# Daughter_Card_v5.net
KiCad netlist of a schematic drawn in EAGLE
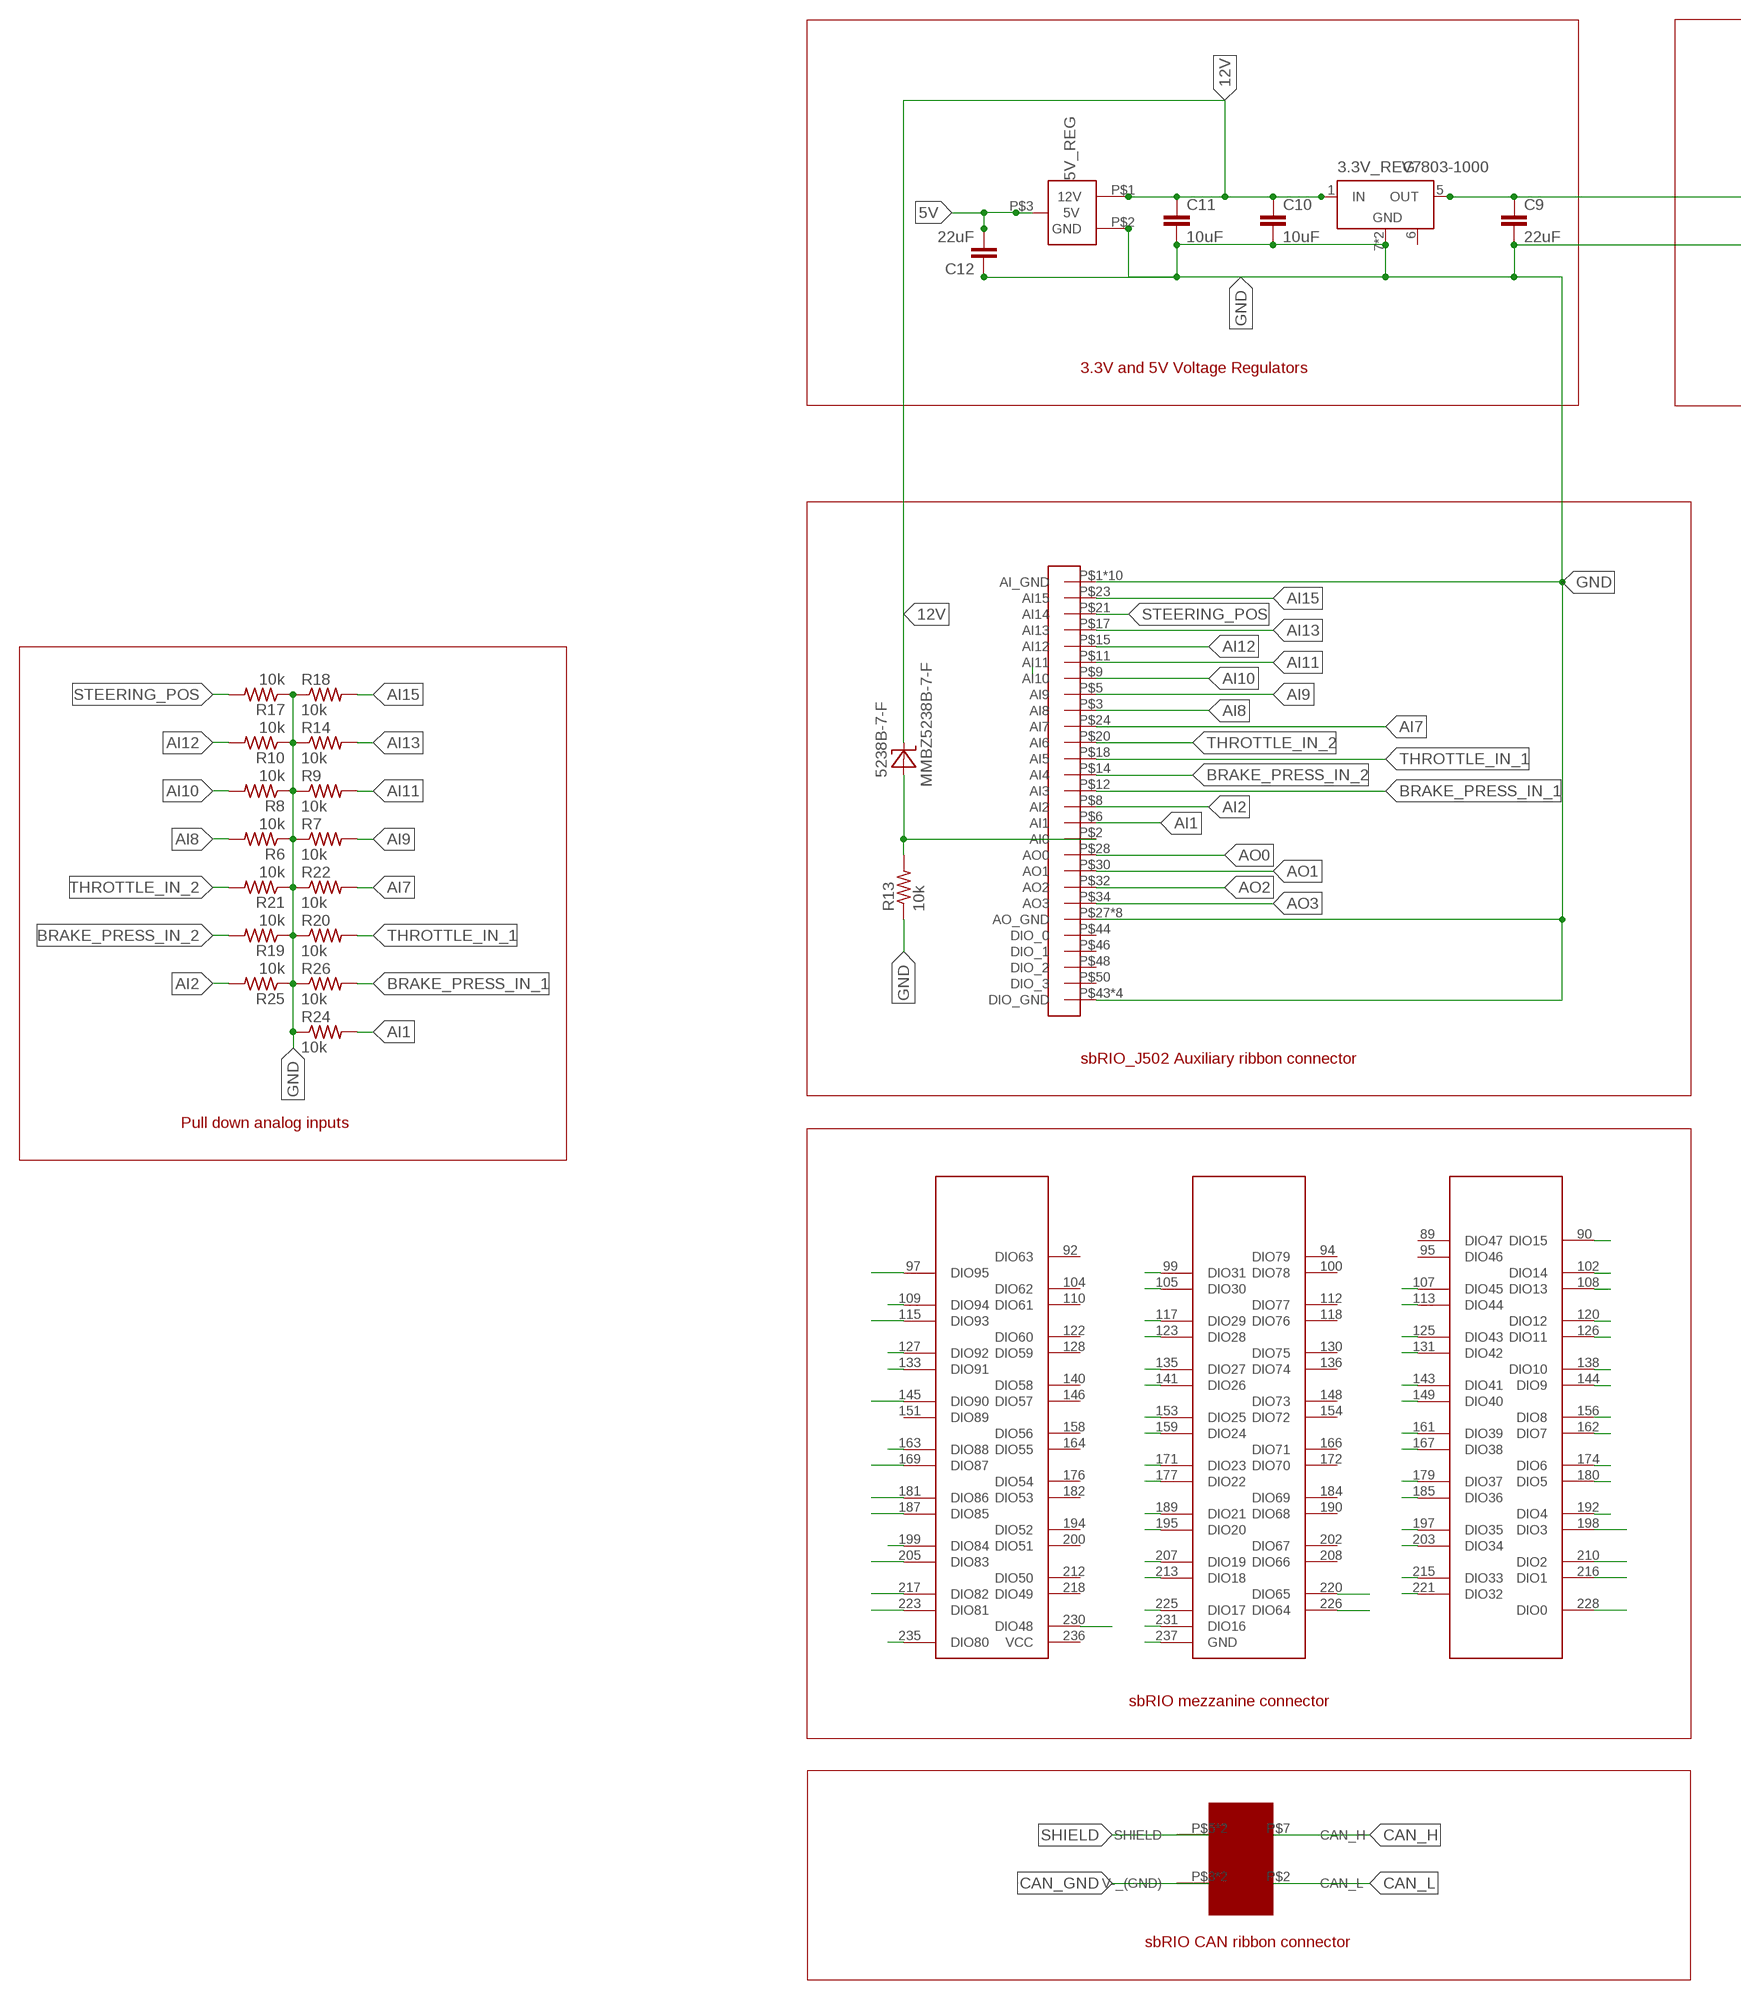
[diagram p0: schematic, sheet 1, part 1 of 2]
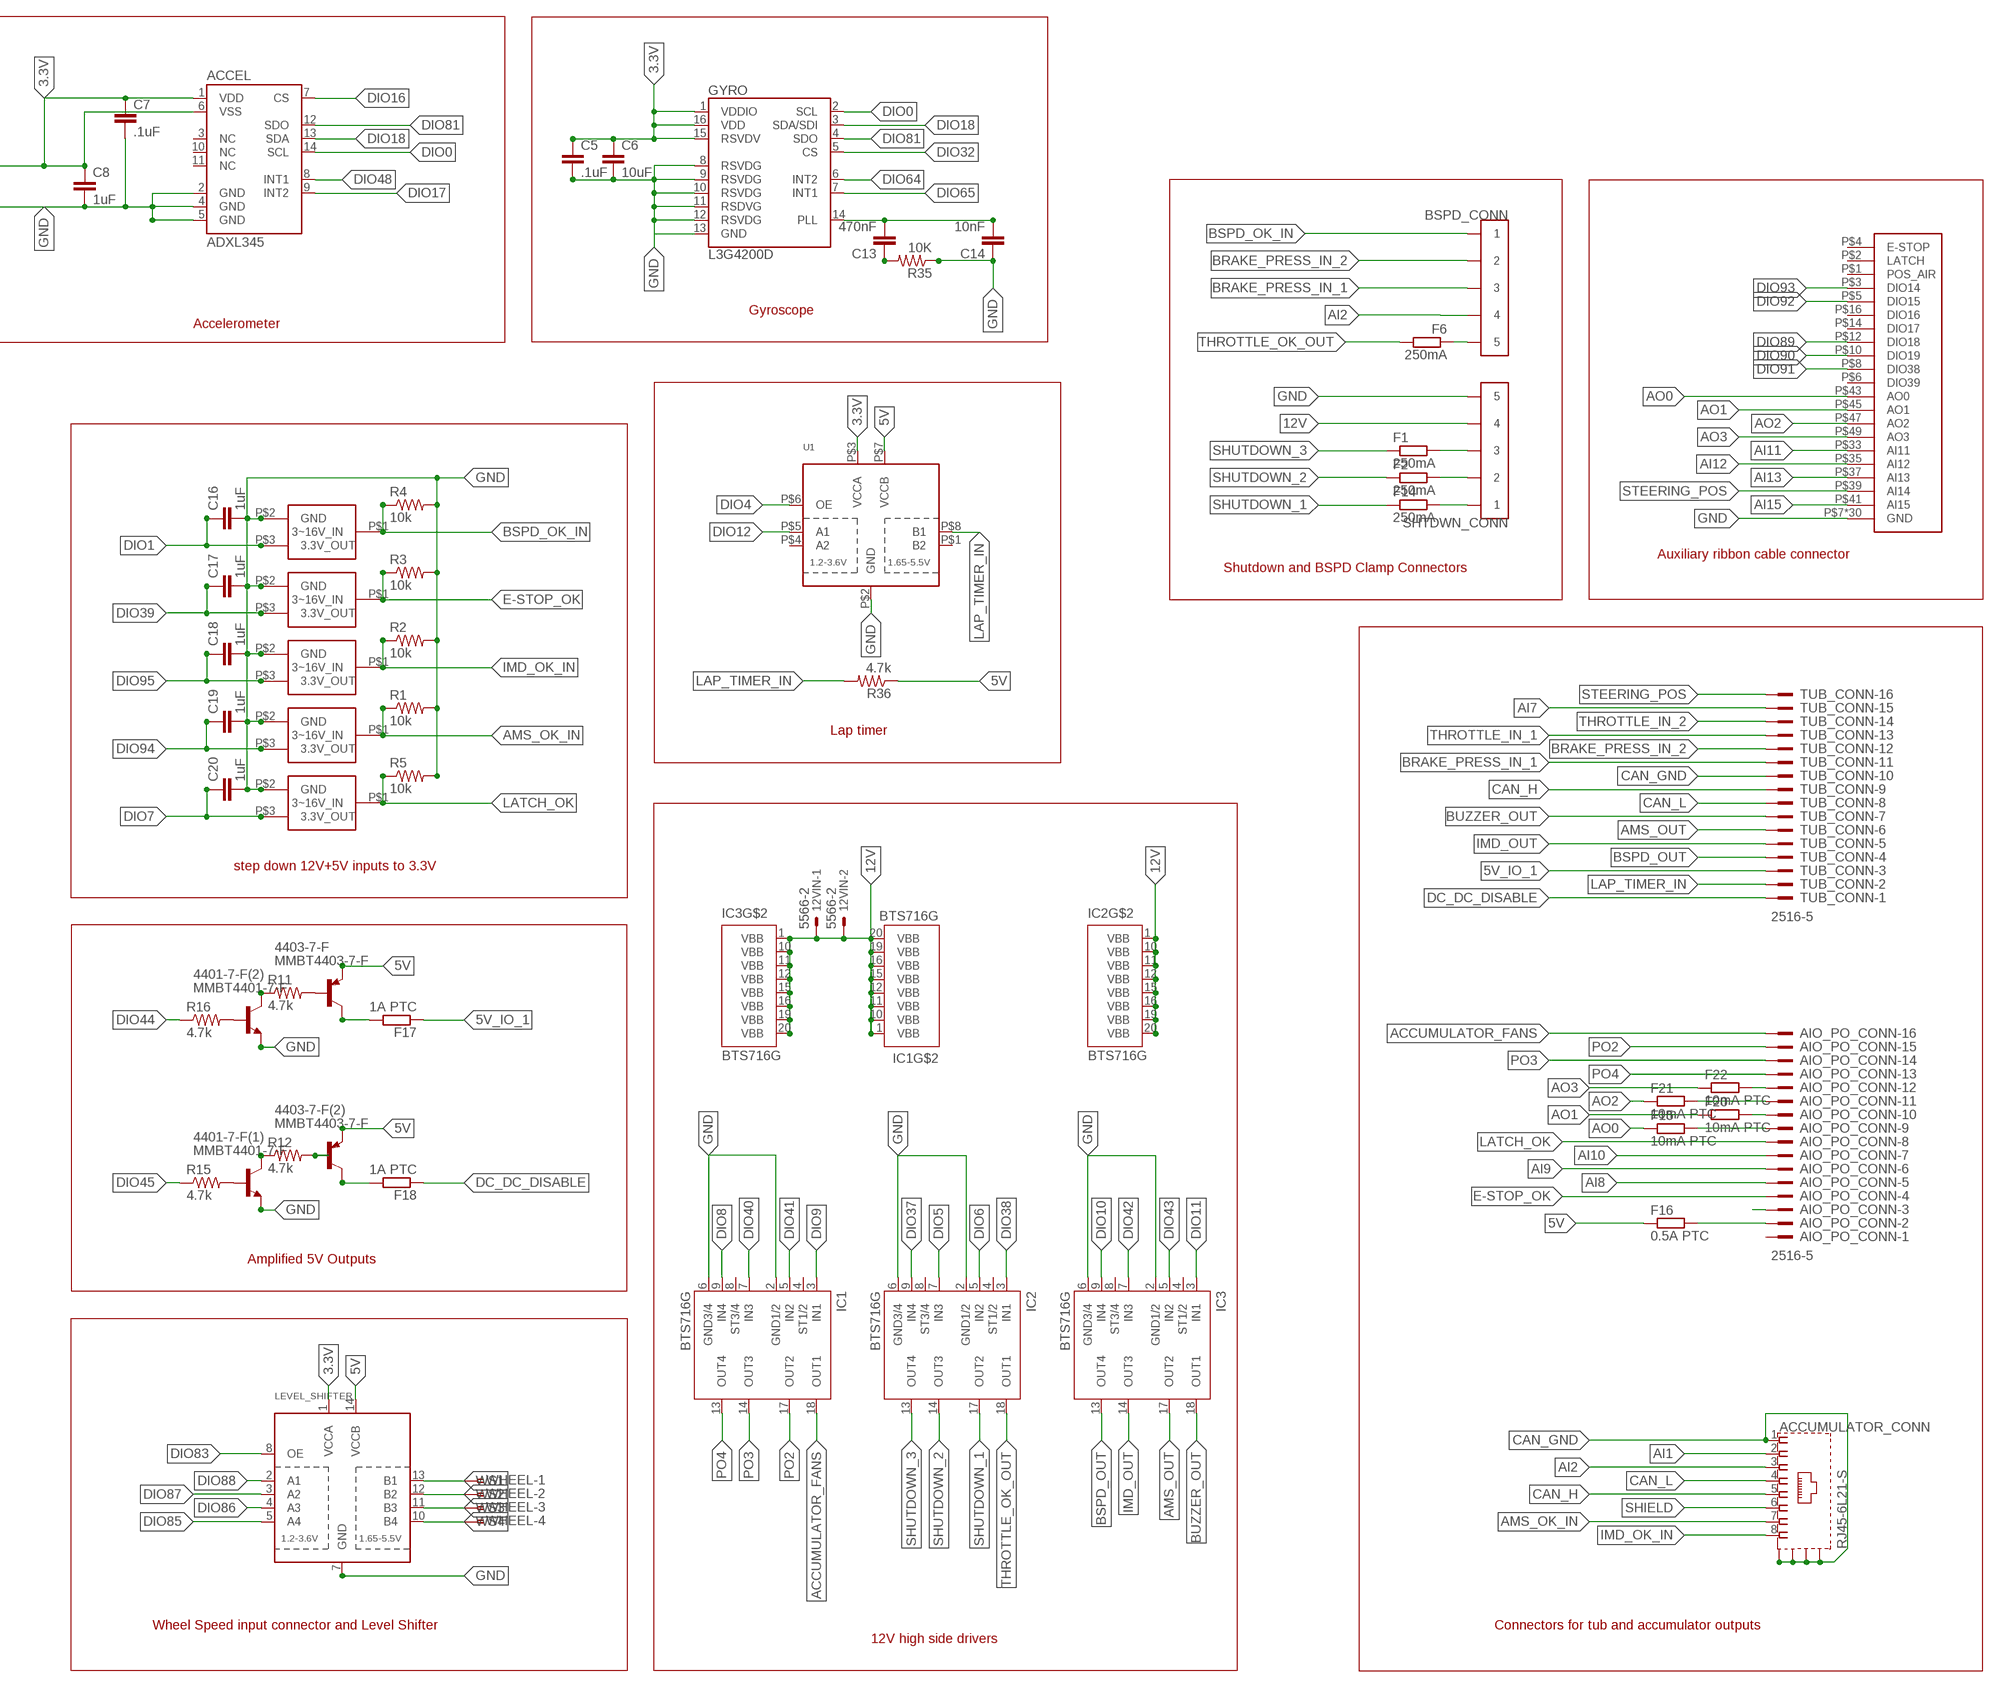
[diagram p1: schematic, sheet 1, part 2 of 2]

(export (version "E")
  (design (tool "Eeschema 10.0.6"))
  (components
    (comp (ref "3.3V_REG")
      (value "V7803-1000")
      (footprint "eagle-import:V78XX-1000")
      (libsource (lib "eagle-import") (part "V7803-1000"))
    )
    (comp (ref "5V_REG")
      (value "V78XX-1500")
      (footprint "eagle-import:V78XX-1500R")
      (libsource (lib "eagle-import") (part "V78XX-1500"))
    )
    (comp (ref "12VIN")
      (value "5566-2")
      (footprint "eagle-import:5566-2")
      (libsource (lib "eagle-import") (part "5566-2"))
    )
    (comp (ref "4401-7-F(1)")
      (value "MMBT4401-7-F")
      (footprint "eagle-import:SOT-23-3")
      (libsource (lib "eagle-import") (part "MMBT4401-7-F"))
    )
    (comp (ref "4401-7-F(2)")
      (value "MMBT4401-7-F")
      (footprint "eagle-import:SOT-23-3")
      (libsource (lib "eagle-import") (part "MMBT4401-7-F"))
    )
    (comp (ref "4403-7-F")
      (value "MMBT4403-7-F")
      (footprint "eagle-import:SOT-23-3")
      (libsource (lib "eagle-import") (part "MMBT4403-7-F"))
    )
    (comp (ref "4403-7-F(2)")
      (value "MMBT4403-7-F")
      (footprint "eagle-import:SOT-23-3")
      (libsource (lib "eagle-import") (part "MMBT4403-7-F"))
    )
    (comp (ref "5225-3.3M5-TR(5)")
      (value "MIC5225-3.3YM5-TR")
      (footprint "eagle-import:SOT-23-3")
      (libsource (lib "eagle-import") (part "MIC5225-3.3YM5-TR"))
    )
    (comp (ref "5238B-7-F")
      (value "MMBZ5238B-7-F")
      (footprint "eagle-import:SOT-23-3")
      (libsource (lib "eagle-import") (part "MMBZ5238B-7-F"))
    )
    (comp (ref "5525-3.3YM5-TR(1)")
      (value "MIC5225-3.3YM5-TR")
      (footprint "eagle-import:SOT-23-3")
      (libsource (lib "eagle-import") (part "MIC5225-3.3YM5-TR"))
    )
    (comp (ref "5525-3.3YM5-TR(2)")
      (value "MIC5225-3.3YM5-TR")
      (footprint "eagle-import:SOT-23-3")
      (libsource (lib "eagle-import") (part "MIC5225-3.3YM5-TR"))
    )
    (comp (ref "5525-3.3YM5-TR(3)")
      (value "MIC5225-3.3YM5-TR")
      (footprint "eagle-import:SOT-23-3")
      (libsource (lib "eagle-import") (part "MIC5225-3.3YM5-TR"))
    )
    (comp (ref "5525-3.3YM5-TR(4)")
      (value "MIC5225-3.3YM5-TR")
      (footprint "eagle-import:SOT-23-3")
      (libsource (lib "eagle-import") (part "MIC5225-3.3YM5-TR"))
    )
    (comp (ref "ACCEL")
      (value "ADXL345")
      (footprint "eagle-import:LGA14")
      (libsource (lib "eagle-import") (part "ADXL345"))
    )
    (comp (ref "ACCUMULATOR_CONN")
      (value "RJ45-6L21-S")
      (footprint "eagle-import:RJ45-SHIELD1")
      (libsource (lib "eagle-import") (part "RJ4521-S-6L"))
    )
    (comp (ref "AIO_PO_CONN")
      (value "2516-5")
      (footprint "eagle-import:PAK100_2500-5-16")
      (fields (field (name "MPN") "D2516-5002-AR"))
      (libsource (lib "eagle-import") (part "2516-5"))
    )
    (comp (ref "BSPD_CONN")
      (value "CONN_5")
      (footprint "eagle-import:CONNECTOR_5")
      (libsource (lib "eagle-import") (part "CONN_5"))
    )
    (comp (ref "C5")
      (value ".1uF")
      (footprint "eagle-import:0603-CAP")
      (libsource (lib "eagle-import") (part "CAP0603-CAP"))
    )
    (comp (ref "C6")
      (value "10uF")
      (footprint "eagle-import:0603-CAP")
      (libsource (lib "eagle-import") (part "CAP0603-CAP"))
    )
    (comp (ref "C7")
      (value ".1uF")
      (footprint "eagle-import:0603-CAP")
      (libsource (lib "eagle-import") (part "CAP0603-CAP"))
    )
    (comp (ref "C8")
      (value "1uF")
      (footprint "eagle-import:0603-CAP")
      (libsource (lib "eagle-import") (part "CAP0603-CAP"))
    )
    (comp (ref "C9")
      (value "22uF")
      (footprint "eagle-import:0603-CAP")
      (libsource (lib "eagle-import") (part "CAP0603-CAP"))
    )
    (comp (ref "C10")
      (value "10uF")
      (footprint "eagle-import:0603-CAP")
      (libsource (lib "eagle-import") (part "CAP0603-CAP"))
    )
    (comp (ref "C11")
      (value "10uF")
      (footprint "eagle-import:0603-CAP")
      (libsource (lib "eagle-import") (part "CAP0603-CAP"))
    )
    (comp (ref "C12")
      (value "22uF")
      (footprint "eagle-import:0603-CAP")
      (libsource (lib "eagle-import") (part "CAP0603-CAP"))
    )
    (comp (ref "C13")
      (value "470nF")
      (footprint "eagle-import:0603-CAP")
      (libsource (lib "eagle-import") (part "CAP0603-CAP"))
    )
    (comp (ref "C14")
      (value "10nF")
      (footprint "eagle-import:0603-CAP")
      (libsource (lib "eagle-import") (part "CAP0603-CAP"))
    )
    (comp (ref "C16")
      (value "1uF")
      (footprint "eagle-import:0603-CAP")
      (libsource (lib "eagle-import") (part "CAP0603-CAP"))
    )
    (comp (ref "C17")
      (value "1uF")
      (footprint "eagle-import:0603-CAP")
      (libsource (lib "eagle-import") (part "CAP0603-CAP"))
    )
    (comp (ref "C18")
      (value "1uF")
      (footprint "eagle-import:0603-CAP")
      (libsource (lib "eagle-import") (part "CAP0603-CAP"))
    )
    (comp (ref "C19")
      (value "1uF")
      (footprint "eagle-import:0603-CAP")
      (libsource (lib "eagle-import") (part "CAP0603-CAP"))
    )
    (comp (ref "C20")
      (value "1uF")
      (footprint "eagle-import:0603-CAP")
      (libsource (lib "eagle-import") (part "CAP0603-CAP"))
    )
    (comp (ref "F1")
      (value "250mA")
      (footprint "eagle-import:R0603")
      (libsource (lib "eagle-import") (part "R-EU_R0603"))
    )
    (comp (ref "F2")
      (value "250mA")
      (footprint "eagle-import:R0603")
      (libsource (lib "eagle-import") (part "R-EU_R0603"))
    )
    (comp (ref "F6")
      (value "250mA")
      (footprint "eagle-import:R0603")
      (libsource (lib "eagle-import") (part "R-EU_R0603"))
    )
    (comp (ref "F14")
      (value "250mA")
      (footprint "eagle-import:R0603")
      (libsource (lib "eagle-import") (part "R-EU_R0603"))
    )
    (comp (ref "F15")
      (value "10mA PTC")
      (footprint "eagle-import:R0402")
      (libsource (lib "eagle-import") (part "R-EU_R0402"))
    )
    (comp (ref "F16")
      (value "0.5A PTC")
      (footprint "eagle-import:R0603")
      (libsource (lib "eagle-import") (part "R-EU_R0603"))
    )
    (comp (ref "F17")
      (value "1A PTC")
      (footprint "eagle-import:R0603")
      (libsource (lib "eagle-import") (part "R-EU_R0603"))
    )
    (comp (ref "F18")
      (value "1A PTC")
      (footprint "eagle-import:R0603")
      (libsource (lib "eagle-import") (part "R-EU_R0603"))
    )
    (comp (ref "F20")
      (value "10mA PTC")
      (footprint "eagle-import:R0402")
      (libsource (lib "eagle-import") (part "R-EU_R0402"))
    )
    (comp (ref "F21")
      (value "10mA PTC")
      (footprint "eagle-import:R0402")
      (libsource (lib "eagle-import") (part "R-EU_R0402"))
    )
    (comp (ref "F22")
      (value "10mA PTC")
      (footprint "eagle-import:R0402")
      (libsource (lib "eagle-import") (part "R-EU_R0402"))
    )
    (comp (ref "GYRO")
      (value "L3G4200D")
      (footprint "eagle-import:LGA16-4X4")
      (libsource (lib "eagle-import") (part "L3G4200D"))
    )
    (comp (ref "IC1")
      (value "BTS716G")
      (footprint "eagle-import:PG-DSO-20")
      (libsource (lib "eagle-import") (part "BTS716G"))
    )
    (comp (ref "IC2")
      (value "BTS716G")
      (footprint "eagle-import:PG-DSO-20")
      (libsource (lib "eagle-import") (part "BTS716G"))
    )
    (comp (ref "IC3")
      (value "BTS716G")
      (footprint "eagle-import:PG-DSO-20")
      (libsource (lib "eagle-import") (part "BTS716G"))
    )
    (comp (ref "LEVEL_SHIFTER")
      (value "TXB0104PWR")
      (footprint "eagle-import:TSSOP14")
      (libsource (lib "eagle-import") (part "TXB0104PWR"))
    )
    (comp (ref "R1")
      (value "10k")
      (footprint "eagle-import:R0402")
      (libsource (lib "eagle-import") (part "R-US_R0402"))
    )
    (comp (ref "R2")
      (value "10k")
      (footprint "eagle-import:R0402")
      (libsource (lib "eagle-import") (part "R-US_R0402"))
    )
    (comp (ref "R3")
      (value "10k")
      (footprint "eagle-import:R0402")
      (libsource (lib "eagle-import") (part "R-US_R0402"))
    )
    (comp (ref "R4")
      (value "10k")
      (footprint "eagle-import:R0402")
      (libsource (lib "eagle-import") (part "R-US_R0402"))
    )
    (comp (ref "R5")
      (value "10k")
      (footprint "eagle-import:R0402")
      (libsource (lib "eagle-import") (part "R-US_R0402"))
    )
    (comp (ref "R6")
      (value "10k")
      (footprint "eagle-import:R0402")
      (libsource (lib "eagle-import") (part "R-US_R0402"))
    )
    (comp (ref "R7")
      (value "10k")
      (footprint "eagle-import:R0402")
      (libsource (lib "eagle-import") (part "R-US_R0402"))
    )
    (comp (ref "R8")
      (value "10k")
      (footprint "eagle-import:R0402")
      (libsource (lib "eagle-import") (part "R-US_R0402"))
    )
    (comp (ref "R9")
      (value "10k")
      (footprint "eagle-import:R0402")
      (libsource (lib "eagle-import") (part "R-US_R0402"))
    )
    (comp (ref "R10")
      (value "10k")
      (footprint "eagle-import:R0402")
      (libsource (lib "eagle-import") (part "R-US_R0402"))
    )
    (comp (ref "R11")
      (value "4.7k")
      (footprint "eagle-import:R0402")
      (libsource (lib "eagle-import") (part "R-US_R0402"))
    )
    (comp (ref "R12")
      (value "4.7k")
      (footprint "eagle-import:R0402")
      (libsource (lib "eagle-import") (part "R-US_R0402"))
    )
    (comp (ref "R13")
      (value "10k")
      (footprint "eagle-import:R0402")
      (libsource (lib "eagle-import") (part "R-US_R0402"))
    )
    (comp (ref "R14")
      (value "10k")
      (footprint "eagle-import:R0402")
      (libsource (lib "eagle-import") (part "R-US_R0402"))
    )
    (comp (ref "R15")
      (value "4.7k")
      (footprint "eagle-import:R0402")
      (libsource (lib "eagle-import") (part "R-US_R0402"))
    )
    (comp (ref "R16")
      (value "4.7k")
      (footprint "eagle-import:R0402")
      (libsource (lib "eagle-import") (part "R-US_R0402"))
    )
    (comp (ref "R17")
      (value "10k")
      (footprint "eagle-import:R0402")
      (libsource (lib "eagle-import") (part "R-US_R0402"))
    )
    (comp (ref "R18")
      (value "10k")
      (footprint "eagle-import:R0402")
      (libsource (lib "eagle-import") (part "R-US_R0402"))
    )
    (comp (ref "R19")
      (value "10k")
      (footprint "eagle-import:R0402")
      (libsource (lib "eagle-import") (part "R-US_R0402"))
    )
    (comp (ref "R20")
      (value "10k")
      (footprint "eagle-import:R0402")
      (libsource (lib "eagle-import") (part "R-US_R0402"))
    )
    (comp (ref "R21")
      (value "10k")
      (footprint "eagle-import:R0402")
      (libsource (lib "eagle-import") (part "R-US_R0402"))
    )
    (comp (ref "R22")
      (value "10k")
      (footprint "eagle-import:R0402")
      (libsource (lib "eagle-import") (part "R-US_R0402"))
    )
    (comp (ref "R24")
      (value "10k")
      (footprint "eagle-import:R0402")
      (libsource (lib "eagle-import") (part "R-US_R0402"))
    )
    (comp (ref "R25")
      (value "10k")
      (footprint "eagle-import:R0402")
      (libsource (lib "eagle-import") (part "R-US_R0402"))
    )
    (comp (ref "R26")
      (value "10k")
      (footprint "eagle-import:R0402")
      (libsource (lib "eagle-import") (part "R-US_R0402"))
    )
    (comp (ref "R35")
      (value "10K")
      (footprint "eagle-import:0603-RES")
      (libsource (lib "eagle-import") (part "RESISTOR0603-RES"))
    )
    (comp (ref "R36")
      (value "4.7k")
      (footprint "eagle-import:R0402")
      (libsource (lib "eagle-import") (part "R-US_R0402"))
    )
    (comp (ref "SBRIO_ANALOG")
      (value "SBRIO_MIO")
      (footprint "eagle-import:SBRIO_J502_J503")
      (libsource (lib "eagle-import") (part "SBRIO_MIO"))
    )
    (comp (ref "SBRIO_AUX")
      (value "SBRIO_AUX")
      (footprint "eagle-import:SBRIO_J502_J503")
      (libsource (lib "eagle-import") (part "SBRIO_AUX"))
    )
    (comp (ref "SBRIO_CAN")
      (value "SBRIO_W500")
      (footprint "eagle-import:SBRIO_W")
      (libsource (lib "eagle-import") (part "SBRIO_W500"))
    )
    (comp (ref "SBRIO_MEZZANINE")
      (value "SBRIO_RMC")
      (footprint "eagle-import:SEAM-40-XX.X-XX-06-X-A")
      (libsource (lib "eagle-import") (part "SBRIO_RMC"))
    )
    (comp (ref "SHTDWN_CONN")
      (value "CONN_5")
      (footprint "eagle-import:CONNECTOR_5")
      (libsource (lib "eagle-import") (part "CONN_5"))
    )
    (comp (ref "TUB_CONN")
      (value "2516-5")
      (footprint "eagle-import:PAK100_2500-5-16")
      (fields (field (name "MPN") "D2516-5002-AR"))
      (libsource (lib "eagle-import") (part "2516-5"))
    )
    (comp (ref "U1")
      (value "TXS0102")
      (footprint "eagle-import:VFSOP-8")
      (libsource (lib "eagle-import") (part "TXS0102"))
    )
    (comp (ref "WHEEL")
      (value "FTOP-4")
      (footprint "eagle-import:FTOP-4")
      (libsource (lib "eagle-import") (part "FTOP-4"))
    )
  )
  (nets
    (net (code "1") (name "/VCC") (class "Default")
      (node (ref "SBRIO_MEZZANINE") (pin "236") (pinfunction "VCC_236") (pintype "power_in"))
    )
    (net (code "2") (name "3.3V") (class "Default")
      (node (ref "3.3V_REG") (pin "5") (pinfunction "OUT_5") (pintype "output"))
      (node (ref "ACCEL") (pin "1") (pinfunction "VDD_1") (pintype "bidirectional"))
      (node (ref "ACCEL") (pin "6") (pinfunction "VSS_6") (pintype "bidirectional"))
      (node (ref "C5") (pin "1") (pinfunction "1_1") (pintype "passive"))
      (node (ref "C6") (pin "1") (pinfunction "1_1") (pintype "passive"))
      (node (ref "C7") (pin "1") (pinfunction "1_1") (pintype "passive"))
      (node (ref "C8") (pin "1") (pinfunction "1_1") (pintype "passive"))
      (node (ref "C9") (pin "1") (pinfunction "1_1") (pintype "passive"))
      (node (ref "GYRO") (pin "1") (pinfunction "VDDIO_1") (pintype "bidirectional"))
      (node (ref "GYRO") (pin "15") (pinfunction "RSVDV_15") (pintype "bidirectional"))
      (node (ref "GYRO") (pin "16") (pinfunction "VDD_16") (pintype "bidirectional"))
      (node (ref "LEVEL_SHIFTER") (pin "1") (pinfunction "VCCA_1") (pintype "bidirectional"))
      (node (ref "U1") (pin "P$3") (pinfunction "VCCA_P$3") (pintype "bidirectional"))
    )
    (net (code "3") (name "5V") (class "Default")
      (node (ref "4403-7-F") (pin "P$3") (pinfunction "E_P$3") (pintype "passive"))
      (node (ref "4403-7-F(2)") (pin "P$3") (pinfunction "E_P$3") (pintype "passive"))
      (node (ref "5V_REG") (pin "P$3") (pinfunction "5V_P$3") (pintype "power_in"))
      (node (ref "C12") (pin "2") (pinfunction "2_2") (pintype "passive"))
      (node (ref "F16") (pin "1") (pinfunction "1_1") (pintype "passive"))
      (node (ref "LEVEL_SHIFTER") (pin "14") (pinfunction "VCCB_14") (pintype "bidirectional"))
      (node (ref "R36") (pin "1") (pinfunction "1_1") (pintype "passive"))
      (node (ref "U1") (pin "P$7") (pinfunction "VCCB_P$7") (pintype "bidirectional"))
    )
    (net (code "4") (name "5V_IO_1") (class "Default")
      (node (ref "F17") (pin "1") (pinfunction "1_1") (pintype "passive"))
      (node (ref "TUB_CONN") (pin "3") (pinfunction "KL_3") (pintype "passive"))
    )
    (net (code "5") (name "12V") (class "Default")
      (node (ref "12VIN") (pin "1") (pinfunction "S_1") (pintype "passive"))
      (node (ref "12VIN") (pin "2") (pinfunction "S_2") (pintype "passive"))
      (node (ref "3.3V_REG") (pin "1") (pinfunction "IN_1") (pintype "input"))
      (node (ref "5238B-7-F") (pin "P$1") (pinfunction "C_P$1") (pintype "passive"))
      (node (ref "5V_REG") (pin "P$1") (pinfunction "12V_P$1") (pintype "power_in"))
      (node (ref "C10") (pin "1") (pinfunction "1_1") (pintype "passive"))
      (node (ref "C11") (pin "1") (pinfunction "1_1") (pintype "passive"))
      (node (ref "IC1") (pin "1") (pinfunction "VBB_1") (pintype "power_in"))
      (node (ref "IC1") (pin "10") (pinfunction "VBB_10") (pintype "power_in"))
      (node (ref "IC1") (pin "11") (pinfunction "VBB_11") (pintype "power_in"))
      (node (ref "IC1") (pin "12") (pinfunction "VBB_12") (pintype "power_in"))
      (node (ref "IC1") (pin "15") (pinfunction "VBB_15") (pintype "power_in"))
      (node (ref "IC1") (pin "16") (pinfunction "VBB_16") (pintype "power_in"))
      (node (ref "IC1") (pin "19") (pinfunction "VBB_19") (pintype "power_in"))
      (node (ref "IC1") (pin "20") (pinfunction "VBB_20") (pintype "power_in"))
      (node (ref "IC2") (pin "1") (pinfunction "VBB_1") (pintype "power_in"))
      (node (ref "IC2") (pin "10") (pinfunction "VBB_10") (pintype "power_in"))
      (node (ref "IC2") (pin "11") (pinfunction "VBB_11") (pintype "power_in"))
      (node (ref "IC2") (pin "12") (pinfunction "VBB_12") (pintype "power_in"))
      (node (ref "IC2") (pin "15") (pinfunction "VBB_15") (pintype "power_in"))
      (node (ref "IC2") (pin "16") (pinfunction "VBB_16") (pintype "power_in"))
      (node (ref "IC2") (pin "19") (pinfunction "VBB_19") (pintype "power_in"))
      (node (ref "IC2") (pin "20") (pinfunction "VBB_20") (pintype "power_in"))
      (node (ref "IC3") (pin "1") (pinfunction "VBB_1") (pintype "power_in"))
      (node (ref "IC3") (pin "10") (pinfunction "VBB_10") (pintype "power_in"))
      (node (ref "IC3") (pin "11") (pinfunction "VBB_11") (pintype "power_in"))
      (node (ref "IC3") (pin "12") (pinfunction "VBB_12") (pintype "power_in"))
      (node (ref "IC3") (pin "15") (pinfunction "VBB_15") (pintype "power_in"))
      (node (ref "IC3") (pin "16") (pinfunction "VBB_16") (pintype "power_in"))
      (node (ref "IC3") (pin "19") (pinfunction "VBB_19") (pintype "power_in"))
      (node (ref "IC3") (pin "20") (pinfunction "VBB_20") (pintype "power_in"))
      (node (ref "SHTDWN_CONN") (pin "7") (pinfunction "4_7") (pintype "bidirectional"))
      (node (ref "SHTDWN_CONN") (pin "8") (pinfunction "4_8") (pintype "bidirectional"))
    )
    (net (code "6") (name "ACCUMULATOR_FANS") (class "Default")
      (node (ref "AIO_PO_CONN") (pin "16") (pinfunction "KL_16") (pintype "passive"))
      (node (ref "IC1") (pin "18") (pinfunction "OUT1_18") (pintype "output"))
    )
    (net (code "7") (name "AI1") (class "Default")
      (node (ref "ACCUMULATOR_CONN") (pin "2") (pinfunction "2_2") (pintype "passive"))
      (node (ref "R24") (pin "2") (pinfunction "2_2") (pintype "passive"))
      (node (ref "SBRIO_ANALOG") (pin "P$6") (pinfunction "AI1_P$6") (pintype "input"))
    )
    (net (code "8") (name "AI2") (class "Default")
      (node (ref "ACCUMULATOR_CONN") (pin "3") (pinfunction "3_3") (pintype "passive"))
      (node (ref "BSPD_CONN") (pin "7") (pinfunction "4_7") (pintype "bidirectional"))
      (node (ref "BSPD_CONN") (pin "8") (pinfunction "4_8") (pintype "bidirectional"))
      (node (ref "R25") (pin "2") (pinfunction "2_2") (pintype "passive"))
      (node (ref "SBRIO_ANALOG") (pin "P$8") (pinfunction "AI2_P$8") (pintype "input"))
    )
    (net (code "9") (name "AI7") (class "Default")
      (node (ref "R22") (pin "2") (pinfunction "2_2") (pintype "passive"))
      (node (ref "SBRIO_ANALOG") (pin "P$24") (pinfunction "AI7_P$24") (pintype "input"))
      (node (ref "TUB_CONN") (pin "15") (pinfunction "KL_15") (pintype "passive"))
    )
    (net (code "10") (name "AI8") (class "Default")
      (node (ref "AIO_PO_CONN") (pin "5") (pinfunction "KL_5") (pintype "passive"))
      (node (ref "R6") (pin "2") (pinfunction "2_2") (pintype "passive"))
      (node (ref "SBRIO_ANALOG") (pin "P$3") (pinfunction "AI8_P$3") (pintype "input"))
    )
    (net (code "11") (name "AI9") (class "Default")
      (node (ref "AIO_PO_CONN") (pin "6") (pinfunction "KL_6") (pintype "passive"))
      (node (ref "R7") (pin "2") (pinfunction "2_2") (pintype "passive"))
      (node (ref "SBRIO_ANALOG") (pin "P$5") (pinfunction "AI9_P$5") (pintype "input"))
    )
    (net (code "12") (name "AI10") (class "Default")
      (node (ref "AIO_PO_CONN") (pin "7") (pinfunction "KL_7") (pintype "passive"))
      (node (ref "R8") (pin "2") (pinfunction "2_2") (pintype "passive"))
      (node (ref "SBRIO_ANALOG") (pin "P$9") (pinfunction "AI10_P$9") (pintype "input"))
    )
    (net (code "13") (name "AI11") (class "Default")
      (node (ref "R9") (pin "2") (pinfunction "2_2") (pintype "passive"))
      (node (ref "SBRIO_ANALOG") (pin "P$11") (pinfunction "AI11_P$11") (pintype "input"))
      (node (ref "SBRIO_AUX") (pin "P$33") (pinfunction "AI11_P$33") (pintype "bidirectional"))
    )
    (net (code "14") (name "AI12") (class "Default")
      (node (ref "R10") (pin "2") (pinfunction "2_2") (pintype "passive"))
      (node (ref "SBRIO_ANALOG") (pin "P$15") (pinfunction "AI12_P$15") (pintype "input"))
      (node (ref "SBRIO_AUX") (pin "P$35") (pinfunction "AI12_P$35") (pintype "bidirectional"))
    )
    (net (code "15") (name "AI13") (class "Default")
      (node (ref "R14") (pin "2") (pinfunction "2_2") (pintype "passive"))
      (node (ref "SBRIO_ANALOG") (pin "P$17") (pinfunction "AI13_P$17") (pintype "input"))
      (node (ref "SBRIO_AUX") (pin "P$37") (pinfunction "AI13_P$37") (pintype "bidirectional"))
    )
    (net (code "16") (name "AI15") (class "Default")
      (node (ref "R18") (pin "2") (pinfunction "2_2") (pintype "passive"))
      (node (ref "SBRIO_ANALOG") (pin "P$23") (pinfunction "AI15_P$23") (pintype "input"))
      (node (ref "SBRIO_AUX") (pin "P$41") (pinfunction "AI15_P$41") (pintype "bidirectional"))
    )
    (net (code "17") (name "AMS_OK_IN") (class "Default")
      (node (ref "5525-3.3YM5-TR(1)") (pin "P$1") (pinfunction "3~{16V_IN}_P$1") (pintype "bidirectional"))
      (node (ref "ACCUMULATOR_CONN") (pin "7") (pinfunction "7_7") (pintype "passive"))
      (node (ref "R1") (pin "1") (pinfunction "1_1") (pintype "passive"))
    )
    (net (code "18") (name "AMS_OUT") (class "Default")
      (node (ref "IC3") (pin "17") (pinfunction "OUT2_17") (pintype "output"))
      (node (ref "TUB_CONN") (pin "6") (pinfunction "KL_6") (pintype "passive"))
    )
    (net (code "19") (name "AO0") (class "Default")
      (node (ref "F15") (pin "1") (pinfunction "1_1") (pintype "passive"))
      (node (ref "SBRIO_ANALOG") (pin "P$28") (pinfunction "AO0_P$28") (pintype "output"))
      (node (ref "SBRIO_AUX") (pin "P$43") (pinfunction "AO0_P$43") (pintype "bidirectional"))
    )
    (net (code "20") (name "AO1") (class "Default")
      (node (ref "F20") (pin "1") (pinfunction "1_1") (pintype "passive"))
      (node (ref "SBRIO_ANALOG") (pin "P$30") (pinfunction "AO1_P$30") (pintype "output"))
      (node (ref "SBRIO_AUX") (pin "P$45") (pinfunction "AO1_P$45") (pintype "bidirectional"))
    )
    (net (code "21") (name "AO2") (class "Default")
      (node (ref "F21") (pin "1") (pinfunction "1_1") (pintype "passive"))
      (node (ref "SBRIO_ANALOG") (pin "P$32") (pinfunction "AO2_P$32") (pintype "output"))
      (node (ref "SBRIO_AUX") (pin "P$47") (pinfunction "AO2_P$47") (pintype "bidirectional"))
    )
    (net (code "22") (name "AO3") (class "Default")
      (node (ref "F22") (pin "1") (pinfunction "1_1") (pintype "passive"))
      (node (ref "SBRIO_ANALOG") (pin "P$34") (pinfunction "AO3_P$34") (pintype "output"))
      (node (ref "SBRIO_AUX") (pin "P$49") (pinfunction "AO3_P$49") (pintype "bidirectional"))
    )
    (net (code "23") (name "BRAKE_PRESS_IN_1") (class "Default")
      (node (ref "BSPD_CONN") (pin "5") (pinfunction "3_5") (pintype "bidirectional"))
      (node (ref "BSPD_CONN") (pin "6") (pinfunction "3_6") (pintype "bidirectional"))
      (node (ref "R26") (pin "2") (pinfunction "2_2") (pintype "passive"))
      (node (ref "SBRIO_ANALOG") (pin "P$12") (pinfunction "AI3_P$12") (pintype "input"))
      (node (ref "TUB_CONN") (pin "11") (pinfunction "KL_11") (pintype "passive"))
    )
    (net (code "24") (name "BRAKE_PRESS_IN_2") (class "Default")
      (node (ref "BSPD_CONN") (pin "3") (pinfunction "2_3") (pintype "bidirectional"))
      (node (ref "BSPD_CONN") (pin "4") (pinfunction "2_4") (pintype "bidirectional"))
      (node (ref "R19") (pin "2") (pinfunction "2_2") (pintype "passive"))
      (node (ref "SBRIO_ANALOG") (pin "P$14") (pinfunction "AI4_P$14") (pintype "input"))
      (node (ref "TUB_CONN") (pin "12") (pinfunction "KL_12") (pintype "passive"))
    )
    (net (code "25") (name "BSPD_OK_IN") (class "Default")
      (node (ref "5525-3.3YM5-TR(3)") (pin "P$1") (pinfunction "3~{16V_IN}_P$1") (pintype "bidirectional"))
      (node (ref "BSPD_CONN") (pin "1") (pinfunction "1_1") (pintype "bidirectional"))
      (node (ref "BSPD_CONN") (pin "2") (pinfunction "1_2") (pintype "bidirectional"))
      (node (ref "R4") (pin "1") (pinfunction "1_1") (pintype "passive"))
    )
    (net (code "26") (name "BSPD_OUT") (class "Default")
      (node (ref "IC3") (pin "13") (pinfunction "OUT4_13") (pintype "output"))
      (node (ref "TUB_CONN") (pin "4") (pinfunction "KL_4") (pintype "passive"))
    )
    (net (code "27") (name "BUZZER_OUT") (class "Default")
      (node (ref "IC3") (pin "18") (pinfunction "OUT1_18") (pintype "output"))
      (node (ref "TUB_CONN") (pin "7") (pinfunction "KL_7") (pintype "passive"))
    )
    (net (code "28") (name "CAN_GND") (class "Default")
      (node (ref "ACCUMULATOR_CONN") (pin "1") (pinfunction "1_1") (pintype "passive"))
      (node (ref "ACCUMULATOR_CONN") (pin "S1") (pinfunction "S_S1") (pintype "passive"))
      (node (ref "ACCUMULATOR_CONN") (pin "S2") (pinfunction "S_S2") (pintype "passive"))
      (node (ref "ACCUMULATOR_CONN") (pin "S3") (pinfunction "S_S3") (pintype "passive"))
      (node (ref "ACCUMULATOR_CONN") (pin "S4") (pinfunction "S_S4") (pintype "passive"))
      (node (ref "SBRIO_CAN") (pin "P$3") (pinfunction "V-_(GND)_P$3") (pintype "power_in"))
      (node (ref "SBRIO_CAN") (pin "P$6") (pinfunction "V-_(GND)_P$6") (pintype "power_in"))
      (node (ref "TUB_CONN") (pin "10") (pinfunction "KL_10") (pintype "passive"))
    )
    (net (code "29") (name "CAN_H") (class "Default")
      (node (ref "ACCUMULATOR_CONN") (pin "5") (pinfunction "5_5") (pintype "passive"))
      (node (ref "SBRIO_CAN") (pin "P$7") (pinfunction "CAN_H_P$7") (pintype "bidirectional"))
      (node (ref "TUB_CONN") (pin "9") (pinfunction "KL_9") (pintype "passive"))
    )
    (net (code "30") (name "CAN_L") (class "Default")
      (node (ref "ACCUMULATOR_CONN") (pin "4") (pinfunction "4_4") (pintype "passive"))
      (node (ref "SBRIO_CAN") (pin "P$2") (pinfunction "CAN_L_P$2") (pintype "bidirectional"))
      (node (ref "TUB_CONN") (pin "8") (pinfunction "KL_8") (pintype "passive"))
    )
    (net (code "31") (name "DC_DC_DISABLE") (class "Default")
      (node (ref "F18") (pin "1") (pinfunction "1_1") (pintype "passive"))
      (node (ref "TUB_CONN") (pin "1") (pinfunction "KL_1") (pintype "passive"))
    )
    (net (code "32") (name "DIO0") (class "Default")
      (node (ref "ACCEL") (pin "14") (pinfunction "SCL_14") (pintype "bidirectional"))
      (node (ref "GYRO") (pin "2") (pinfunction "SCL_2") (pintype "bidirectional"))
      (node (ref "SBRIO_MEZZANINE") (pin "228") (pinfunction "DIO0_228") (pintype "bidirectional"))
    )
    (net (code "33") (name "DIO1") (class "Default")
      (node (ref "5525-3.3YM5-TR(3)") (pin "P$3") (pinfunction "3.3V_OUT_P$3") (pintype "bidirectional"))
      (node (ref "C16") (pin "1") (pinfunction "1_1") (pintype "passive"))
      (node (ref "SBRIO_MEZZANINE") (pin "216") (pinfunction "DIO1_216") (pintype "bidirectional"))
    )
    (net (code "34") (name "DIO4") (class "Default")
      (node (ref "SBRIO_MEZZANINE") (pin "192") (pinfunction "DIO4_192") (pintype "bidirectional"))
      (node (ref "U1") (pin "P$6") (pinfunction "OE_P$6") (pintype "bidirectional"))
    )
    (net (code "35") (name "DIO5") (class "Default")
      (node (ref "IC2") (pin "7") (pinfunction "IN3_7") (pintype "input"))
      (node (ref "SBRIO_MEZZANINE") (pin "180") (pinfunction "DIO5_180") (pintype "bidirectional"))
    )
    (net (code "36") (name "DIO6") (class "Default")
      (node (ref "IC2") (pin "5") (pinfunction "IN2_5") (pintype "input"))
      (node (ref "SBRIO_MEZZANINE") (pin "174") (pinfunction "DIO6_174") (pintype "bidirectional"))
    )
    (net (code "37") (name "DIO7") (class "Default")
      (node (ref "5525-3.3YM5-TR(2)") (pin "P$3") (pinfunction "3.3V_OUT_P$3") (pintype "bidirectional"))
      (node (ref "C20") (pin "1") (pinfunction "1_1") (pintype "passive"))
      (node (ref "SBRIO_MEZZANINE") (pin "162") (pinfunction "DIO7_162") (pintype "bidirectional"))
    )
    (net (code "38") (name "DIO8") (class "Default")
      (node (ref "IC1") (pin "9") (pinfunction "IN4_9") (pintype "input"))
      (node (ref "SBRIO_MEZZANINE") (pin "156") (pinfunction "DIO8_156") (pintype "bidirectional"))
    )
    (net (code "39") (name "DIO9") (class "Default")
      (node (ref "IC1") (pin "3") (pinfunction "IN1_3") (pintype "input"))
      (node (ref "SBRIO_MEZZANINE") (pin "144") (pinfunction "DIO9_144") (pintype "bidirectional"))
    )
    (net (code "40") (name "DIO10") (class "Default")
      (node (ref "IC3") (pin "9") (pinfunction "IN4_9") (pintype "input"))
      (node (ref "SBRIO_MEZZANINE") (pin "138") (pinfunction "DIO10_138") (pintype "bidirectional"))
    )
    (net (code "41") (name "DIO11") (class "Default")
      (node (ref "IC3") (pin "3") (pinfunction "IN1_3") (pintype "input"))
      (node (ref "SBRIO_MEZZANINE") (pin "126") (pinfunction "DIO11_126") (pintype "bidirectional"))
    )
    (net (code "42") (name "DIO12") (class "Default")
      (node (ref "SBRIO_MEZZANINE") (pin "120") (pinfunction "DIO12_120") (pintype "bidirectional"))
      (node (ref "U1") (pin "P$5") (pinfunction "A1_P$5") (pintype "bidirectional"))
    )
    (net (code "43") (name "DIO16") (class "Default")
      (node (ref "ACCEL") (pin "7") (pinfunction "CS_7") (pintype "bidirectional"))
      (node (ref "SBRIO_MEZZANINE") (pin "231") (pinfunction "DIO16_231") (pintype "bidirectional"))
    )
    (net (code "44") (name "DIO17") (class "Default")
      (node (ref "ACCEL") (pin "9") (pinfunction "INT2_9") (pintype "bidirectional"))
      (node (ref "SBRIO_MEZZANINE") (pin "225") (pinfunction "DIO17_225") (pintype "bidirectional"))
    )
    (net (code "45") (name "DIO18") (class "Default")
      (node (ref "ACCEL") (pin "13") (pinfunction "SDA_13") (pintype "bidirectional"))
      (node (ref "GYRO") (pin "3") (pinfunction "SDA/SDI_3") (pintype "bidirectional"))
      (node (ref "SBRIO_MEZZANINE") (pin "213") (pinfunction "DIO18_213") (pintype "bidirectional"))
    )
    (net (code "46") (name "DIO32") (class "Default")
      (node (ref "GYRO") (pin "5") (pinfunction "CS_5") (pintype "bidirectional"))
      (node (ref "SBRIO_MEZZANINE") (pin "221") (pinfunction "DIO32_221") (pintype "bidirectional"))
    )
    (net (code "47") (name "DIO37") (class "Default")
      (node (ref "IC2") (pin "9") (pinfunction "IN4_9") (pintype "input"))
      (node (ref "SBRIO_MEZZANINE") (pin "179") (pinfunction "DIO37_179") (pintype "bidirectional"))
    )
    (net (code "48") (name "DIO38") (class "Default")
      (node (ref "IC2") (pin "3") (pinfunction "IN1_3") (pintype "input"))
      (node (ref "SBRIO_MEZZANINE") (pin "167") (pinfunction "DIO38_167") (pintype "bidirectional"))
    )
    (net (code "49") (name "DIO39") (class "Default")
      (node (ref "5525-3.3YM5-TR(4)") (pin "P$3") (pinfunction "3.3V_OUT_P$3") (pintype "bidirectional"))
      (node (ref "C17") (pin "1") (pinfunction "1_1") (pintype "passive"))
      (node (ref "SBRIO_MEZZANINE") (pin "161") (pinfunction "DIO39_161") (pintype "bidirectional"))
    )
    (net (code "50") (name "DIO40") (class "Default")
      (node (ref "IC1") (pin "7") (pinfunction "IN3_7") (pintype "input"))
      (node (ref "SBRIO_MEZZANINE") (pin "149") (pinfunction "DIO40_149") (pintype "bidirectional"))
    )
    (net (code "51") (name "DIO41") (class "Default")
      (node (ref "IC1") (pin "5") (pinfunction "IN2_5") (pintype "input"))
      (node (ref "SBRIO_MEZZANINE") (pin "143") (pinfunction "DIO41_143") (pintype "bidirectional"))
    )
    (net (code "52") (name "DIO42") (class "Default")
      (node (ref "IC3") (pin "7") (pinfunction "IN3_7") (pintype "input"))
      (node (ref "SBRIO_MEZZANINE") (pin "131") (pinfunction "DIO42_131") (pintype "bidirectional"))
    )
    (net (code "53") (name "DIO43") (class "Default")
      (node (ref "IC3") (pin "5") (pinfunction "IN2_5") (pintype "input"))
      (node (ref "SBRIO_MEZZANINE") (pin "125") (pinfunction "DIO43_125") (pintype "bidirectional"))
    )
    (net (code "54") (name "DIO44") (class "Default")
      (node (ref "R16") (pin "1") (pinfunction "1_1") (pintype "passive"))
      (node (ref "SBRIO_MEZZANINE") (pin "113") (pinfunction "DIO44_113") (pintype "bidirectional"))
    )
    (net (code "55") (name "DIO45") (class "Default")
      (node (ref "R15") (pin "1") (pinfunction "1_1") (pintype "passive"))
      (node (ref "SBRIO_MEZZANINE") (pin "107") (pinfunction "DIO45_107") (pintype "bidirectional"))
    )
    (net (code "56") (name "DIO48") (class "Default")
      (node (ref "ACCEL") (pin "8") (pinfunction "INT1_8") (pintype "bidirectional"))
      (node (ref "SBRIO_MEZZANINE") (pin "230") (pinfunction "DIO48_230") (pintype "bidirectional"))
    )
    (net (code "57") (name "DIO64") (class "Default")
      (node (ref "GYRO") (pin "6") (pinfunction "INT2_6") (pintype "bidirectional"))
      (node (ref "SBRIO_MEZZANINE") (pin "226") (pinfunction "DIO64_226") (pintype "bidirectional"))
    )
    (net (code "58") (name "DIO65") (class "Default")
      (node (ref "GYRO") (pin "7") (pinfunction "INT1_7") (pintype "bidirectional"))
      (node (ref "SBRIO_MEZZANINE") (pin "220") (pinfunction "DIO65_220") (pintype "bidirectional"))
    )
    (net (code "59") (name "DIO81") (class "Default")
      (node (ref "ACCEL") (pin "12") (pinfunction "SDO_12") (pintype "bidirectional"))
      (node (ref "GYRO") (pin "4") (pinfunction "SDO_4") (pintype "bidirectional"))
      (node (ref "SBRIO_MEZZANINE") (pin "223") (pinfunction "DIO81_223") (pintype "bidirectional"))
    )
    (net (code "60") (name "DIO83") (class "Default")
      (node (ref "LEVEL_SHIFTER") (pin "8") (pinfunction "OE_8") (pintype "bidirectional"))
      (node (ref "SBRIO_MEZZANINE") (pin "205") (pinfunction "DIO83_205") (pintype "bidirectional"))
    )
    (net (code "61") (name "DIO85") (class "Default")
      (node (ref "LEVEL_SHIFTER") (pin "5") (pinfunction "A4_5") (pintype "bidirectional"))
      (node (ref "SBRIO_MEZZANINE") (pin "187") (pinfunction "DIO85_187") (pintype "bidirectional"))
    )
    (net (code "62") (name "DIO86") (class "Default")
      (node (ref "LEVEL_SHIFTER") (pin "4") (pinfunction "A3_4") (pintype "bidirectional"))
      (node (ref "SBRIO_MEZZANINE") (pin "181") (pinfunction "DIO86_181") (pintype "bidirectional"))
    )
    (net (code "63") (name "DIO87") (class "Default")
      (node (ref "LEVEL_SHIFTER") (pin "3") (pinfunction "A2_3") (pintype "bidirectional"))
      (node (ref "SBRIO_MEZZANINE") (pin "169") (pinfunction "DIO87_169") (pintype "bidirectional"))
    )
    (net (code "64") (name "DIO88") (class "Default")
      (node (ref "LEVEL_SHIFTER") (pin "2") (pinfunction "A1_2") (pintype "bidirectional"))
      (node (ref "SBRIO_MEZZANINE") (pin "163") (pinfunction "DIO88_163") (pintype "bidirectional"))
    )
    (net (code "65") (name "DIO89") (class "Default")
      (node (ref "SBRIO_AUX") (pin "P$12") (pinfunction "DIO18_P$12") (pintype "bidirectional"))
    )
    (net (code "66") (name "DIO90") (class "Default")
      (node (ref "SBRIO_AUX") (pin "P$10") (pinfunction "DIO19_P$10") (pintype "bidirectional"))
      (node (ref "SBRIO_MEZZANINE") (pin "145") (pinfunction "DIO90_145") (pintype "bidirectional"))
    )
    (net (code "67") (name "DIO91") (class "Default")
      (node (ref "SBRIO_AUX") (pin "P$8") (pinfunction "DIO38_P$8") (pintype "bidirectional"))
      (node (ref "SBRIO_MEZZANINE") (pin "133") (pinfunction "DIO91_133") (pintype "bidirectional"))
    )
    (net (code "68") (name "DIO92") (class "Default")
      (node (ref "SBRIO_AUX") (pin "P$5") (pinfunction "DIO15_P$5") (pintype "bidirectional"))
      (node (ref "SBRIO_MEZZANINE") (pin "127") (pinfunction "DIO92_127") (pintype "bidirectional"))
    )
    (net (code "69") (name "DIO93") (class "Default")
      (node (ref "SBRIO_AUX") (pin "P$3") (pinfunction "DIO14_P$3") (pintype "bidirectional"))
      (node (ref "SBRIO_MEZZANINE") (pin "115") (pinfunction "DIO93_115") (pintype "bidirectional"))
    )
    (net (code "70") (name "DIO94") (class "Default")
      (node (ref "5525-3.3YM5-TR(1)") (pin "P$3") (pinfunction "3.3V_OUT_P$3") (pintype "bidirectional"))
      (node (ref "C19") (pin "1") (pinfunction "1_1") (pintype "passive"))
      (node (ref "SBRIO_MEZZANINE") (pin "109") (pinfunction "DIO94_109") (pintype "bidirectional"))
    )
    (net (code "71") (name "DIO95") (class "Default")
      (node (ref "5225-3.3M5-TR(5)") (pin "P$3") (pinfunction "3.3V_OUT_P$3") (pintype "bidirectional"))
      (node (ref "C18") (pin "1") (pinfunction "1_1") (pintype "passive"))
      (node (ref "SBRIO_MEZZANINE") (pin "97") (pinfunction "DIO95_97") (pintype "bidirectional"))
    )
    (net (code "72") (name "E-STOP_OK") (class "Default")
      (node (ref "5525-3.3YM5-TR(4)") (pin "P$1") (pinfunction "3~{16V_IN}_P$1") (pintype "bidirectional"))
      (node (ref "AIO_PO_CONN") (pin "4") (pinfunction "KL_4") (pintype "passive"))
      (node (ref "R3") (pin "1") (pinfunction "1_1") (pintype "passive"))
    )
    (net (code "73") (name "GND") (class "Default")
      (node (ref "3.3V_REG") (pin "7") (pinfunction "GND_7") (pintype "power_in"))
      (node (ref "3.3V_REG") (pin "9") (pinfunction "GND_9") (pintype "power_in"))
      (node (ref "4401-7-F(1)") (pin "P$3") (pinfunction "E_P$3") (pintype "passive"))
      (node (ref "4401-7-F(2)") (pin "P$3") (pinfunction "E_P$3") (pintype "passive"))
      (node (ref "5225-3.3M5-TR(5)") (pin "P$2") (pinfunction "GND_P$2") (pintype "bidirectional"))
      (node (ref "5525-3.3YM5-TR(1)") (pin "P$2") (pinfunction "GND_P$2") (pintype "bidirectional"))
      (node (ref "5525-3.3YM5-TR(2)") (pin "P$2") (pinfunction "GND_P$2") (pintype "bidirectional"))
      (node (ref "5525-3.3YM5-TR(3)") (pin "P$2") (pinfunction "GND_P$2") (pintype "bidirectional"))
      (node (ref "5525-3.3YM5-TR(4)") (pin "P$2") (pinfunction "GND_P$2") (pintype "bidirectional"))
      (node (ref "5V_REG") (pin "P$2") (pinfunction "GND_P$2") (pintype "power_in"))
      (node (ref "ACCEL") (pin "2") (pinfunction "GND_2") (pintype "bidirectional"))
      (node (ref "ACCEL") (pin "4") (pinfunction "GND_4") (pintype "bidirectional"))
      (node (ref "ACCEL") (pin "5") (pinfunction "GND_5") (pintype "bidirectional"))
      (node (ref "C10") (pin "2") (pinfunction "2_2") (pintype "passive"))
      (node (ref "C11") (pin "2") (pinfunction "2_2") (pintype "passive"))
      (node (ref "C12") (pin "1") (pinfunction "1_1") (pintype "passive"))
      (node (ref "C14") (pin "1") (pinfunction "1_1") (pintype "passive"))
      (node (ref "C16") (pin "2") (pinfunction "2_2") (pintype "passive"))
      (node (ref "C17") (pin "2") (pinfunction "2_2") (pintype "passive"))
      (node (ref "C18") (pin "2") (pinfunction "2_2") (pintype "passive"))
      (node (ref "C19") (pin "2") (pinfunction "2_2") (pintype "passive"))
      (node (ref "C20") (pin "2") (pinfunction "2_2") (pintype "passive"))
      (node (ref "C5") (pin "2") (pinfunction "2_2") (pintype "passive"))
      (node (ref "C6") (pin "2") (pinfunction "2_2") (pintype "passive"))
      (node (ref "C7") (pin "2") (pinfunction "2_2") (pintype "passive"))
      (node (ref "C8") (pin "2") (pinfunction "2_2") (pintype "passive"))
      (node (ref "C9") (pin "2") (pinfunction "2_2") (pintype "passive"))
      (node (ref "GYRO") (pin "10") (pinfunction "RSVDG_10") (pintype "bidirectional"))
      (node (ref "GYRO") (pin "11") (pinfunction "RSDVG_11") (pintype "bidirectional"))
      (node (ref "GYRO") (pin "12") (pinfunction "RSVDG_12") (pintype "bidirectional"))
      (node (ref "GYRO") (pin "13") (pinfunction "GND_13") (pintype "bidirectional"))
      (node (ref "GYRO") (pin "8") (pinfunction "RSVDG_8") (pintype "bidirectional"))
      (node (ref "GYRO") (pin "9") (pinfunction "RSVDG_9") (pintype "bidirectional"))
      (node (ref "IC1") (pin "2") (pinfunction "GND1/2_2") (pintype "input"))
      (node (ref "IC1") (pin "6") (pinfunction "GND3/4_6") (pintype "input"))
      (node (ref "IC2") (pin "2") (pinfunction "GND1/2_2") (pintype "input"))
      (node (ref "IC2") (pin "6") (pinfunction "GND3/4_6") (pintype "input"))
      (node (ref "IC3") (pin "2") (pinfunction "GND1/2_2") (pintype "input"))
      (node (ref "IC3") (pin "6") (pinfunction "GND3/4_6") (pintype "input"))
      (node (ref "LEVEL_SHIFTER") (pin "7") (pinfunction "GND_7") (pintype "bidirectional"))
      (node (ref "R1") (pin "2") (pinfunction "2_2") (pintype "passive"))
      (node (ref "R10") (pin "1") (pinfunction "1_1") (pintype "passive"))
      (node (ref "R13") (pin "1") (pinfunction "1_1") (pintype "passive"))
      (node (ref "R14") (pin "1") (pinfunction "1_1") (pintype "passive"))
      (node (ref "R17") (pin "1") (pinfunction "1_1") (pintype "passive"))
      (node (ref "R18") (pin "1") (pinfunction "1_1") (pintype "passive"))
      (node (ref "R19") (pin "1") (pinfunction "1_1") (pintype "passive"))
      (node (ref "R2") (pin "2") (pinfunction "2_2") (pintype "passive"))
      (node (ref "R20") (pin "1") (pinfunction "1_1") (pintype "passive"))
      (node (ref "R21") (pin "1") (pinfunction "1_1") (pintype "passive"))
      (node (ref "R22") (pin "1") (pinfunction "1_1") (pintype "passive"))
      (node (ref "R24") (pin "1") (pinfunction "1_1") (pintype "passive"))
      (node (ref "R25") (pin "1") (pinfunction "1_1") (pintype "passive"))
      (node (ref "R26") (pin "1") (pinfunction "1_1") (pintype "passive"))
      (node (ref "R3") (pin "2") (pinfunction "2_2") (pintype "passive"))
      (node (ref "R35") (pin "1") (pinfunction "1_1") (pintype "passive"))
      (node (ref "R4") (pin "2") (pinfunction "2_2") (pintype "passive"))
      (node (ref "R5") (pin "2") (pinfunction "2_2") (pintype "passive"))
      (node (ref "R6") (pin "1") (pinfunction "1_1") (pintype "passive"))
      (node (ref "R7") (pin "1") (pinfunction "1_1") (pintype "passive"))
      (node (ref "R8") (pin "1") (pinfunction "1_1") (pintype "passive"))
      (node (ref "R9") (pin "1") (pinfunction "1_1") (pintype "passive"))
      (node (ref "SBRIO_ANALOG") (pin "P$1") (pinfunction "AI_GND_P$1") (pintype "input"))
      (node (ref "SBRIO_ANALOG") (pin "P$10") (pinfunction "AI_GND_P$10") (pintype "input"))
      (node (ref "SBRIO_ANALOG") (pin "P$13") (pinfunction "AI_GND_P$13") (pintype "input"))
      (node (ref "SBRIO_ANALOG") (pin "P$16") (pinfunction "AI_GND_P$16") (pintype "input"))
      (node (ref "SBRIO_ANALOG") (pin "P$19") (pinfunction "AI_GND_P$19") (pintype "input"))
      (node (ref "SBRIO_ANALOG") (pin "P$22") (pinfunction "AI_GND_P$22") (pintype "input"))
      (node (ref "SBRIO_ANALOG") (pin "P$25") (pinfunction "AI_GND_P$25") (pintype "input"))
      (node (ref "SBRIO_ANALOG") (pin "P$26") (pinfunction "AI_GND_P$26") (pintype "input"))
      (node (ref "SBRIO_ANALOG") (pin "P$27") (pinfunction "AO_GND_P$27") (pintype "power_in"))
      (node (ref "SBRIO_ANALOG") (pin "P$29") (pinfunction "AO_GND_P$29") (pintype "power_in"))
      (node (ref "SBRIO_ANALOG") (pin "P$31") (pinfunction "AO_GND_P$31") (pintype "power_in"))
      (node (ref "SBRIO_ANALOG") (pin "P$33") (pinfunction "AO_GND_P$33") (pintype "power_in"))
      (node (ref "SBRIO_ANALOG") (pin "P$35") (pinfunction "AO_GND_P$35") (pintype "power_in"))
      (node (ref "SBRIO_ANALOG") (pin "P$37") (pinfunction "AO_GND_P$37") (pintype "power_in"))
      (node (ref "SBRIO_ANALOG") (pin "P$39") (pinfunction "AO_GND_P$39") (pintype "power_in"))
      (node (ref "SBRIO_ANALOG") (pin "P$4") (pinfunction "AI_GND_P$4") (pintype "input"))
      (node (ref "SBRIO_ANALOG") (pin "P$41") (pinfunction "AO_GND_P$41") (pintype "power_in"))
      (node (ref "SBRIO_ANALOG") (pin "P$43") (pinfunction "DIO_GND_P$43") (pintype "power_in"))
      (node (ref "SBRIO_ANALOG") (pin "P$45") (pinfunction "DIO_GND_P$45") (pintype "power_in"))
      (node (ref "SBRIO_ANALOG") (pin "P$47") (pinfunction "DIO_GND_P$47") (pintype "power_in"))
      (node (ref "SBRIO_ANALOG") (pin "P$49") (pinfunction "DIO_GND_P$49") (pintype "power_in"))
      (node (ref "SBRIO_ANALOG") (pin "P$7") (pinfunction "AI_GND_P$7") (pintype "input"))
      (node (ref "SBRIO_AUX") (pin "P$11") (pinfunction "GND_P$11") (pintype "bidirectional"))
      (node (ref "SBRIO_AUX") (pin "P$13") (pinfunction "GND_P$13") (pintype "bidirectional"))
      (node (ref "SBRIO_AUX") (pin "P$15") (pinfunction "GND_P$15") (pintype "bidirectional"))
      (node (ref "SBRIO_AUX") (pin "P$17") (pinfunction "GND_P$17") (pintype "bidirectional"))
      (node (ref "SBRIO_AUX") (pin "P$18") (pinfunction "GND_P$18") (pintype "bidirectional"))
      (node (ref "SBRIO_AUX") (pin "P$19") (pinfunction "GND_P$19") (pintype "bidirectional"))
      (node (ref "SBRIO_AUX") (pin "P$20") (pinfunction "GND_P$20") (pintype "bidirectional"))
      (node (ref "SBRIO_AUX") (pin "P$21") (pinfunction "GND_P$21") (pintype "bidirectional"))
      (node (ref "SBRIO_AUX") (pin "P$22") (pinfunction "GND_P$22") (pintype "bidirectional"))
      (node (ref "SBRIO_AUX") (pin "P$23") (pinfunction "GND_P$23") (pintype "bidirectional"))
      (node (ref "SBRIO_AUX") (pin "P$24") (pinfunction "GND_P$24") (pintype "bidirectional"))
      (node (ref "SBRIO_AUX") (pin "P$25") (pinfunction "GND_P$25") (pintype "bidirectional"))
      (node (ref "SBRIO_AUX") (pin "P$26") (pinfunction "GND_P$26") (pintype "bidirectional"))
      (node (ref "SBRIO_AUX") (pin "P$27") (pinfunction "GND_P$27") (pintype "bidirectional"))
      (node (ref "SBRIO_AUX") (pin "P$28") (pinfunction "GND_P$28") (pintype "bidirectional"))
      (node (ref "SBRIO_AUX") (pin "P$29") (pinfunction "GND_P$29") (pintype "bidirectional"))
      (node (ref "SBRIO_AUX") (pin "P$30") (pinfunction "GND_P$30") (pintype "bidirectional"))
      (node (ref "SBRIO_AUX") (pin "P$31") (pinfunction "GND_P$31") (pintype "bidirectional"))
      (node (ref "SBRIO_AUX") (pin "P$32") (pinfunction "GND_P$32") (pintype "bidirectional"))
      (node (ref "SBRIO_AUX") (pin "P$34") (pinfunction "GND_P$34") (pintype "bidirectional"))
      (node (ref "SBRIO_AUX") (pin "P$36") (pinfunction "GND_P$36") (pintype "bidirectional"))
      (node (ref "SBRIO_AUX") (pin "P$38") (pinfunction "GND_P$38") (pintype "bidirectional"))
      (node (ref "SBRIO_AUX") (pin "P$40") (pinfunction "GND_P$40") (pintype "bidirectional"))
      (node (ref "SBRIO_AUX") (pin "P$42") (pinfunction "GND_P$42") (pintype "bidirectional"))
      (node (ref "SBRIO_AUX") (pin "P$44") (pinfunction "GND_P$44") (pintype "bidirectional"))
      (node (ref "SBRIO_AUX") (pin "P$46") (pinfunction "GND_P$46") (pintype "bidirectional"))
      (node (ref "SBRIO_AUX") (pin "P$48") (pinfunction "GND_P$48") (pintype "bidirectional"))
      (node (ref "SBRIO_AUX") (pin "P$50") (pinfunction "GND_P$50") (pintype "bidirectional"))
      (node (ref "SBRIO_AUX") (pin "P$7") (pinfunction "GND_P$7") (pintype "bidirectional"))
      (node (ref "SBRIO_AUX") (pin "P$9") (pinfunction "GND_P$9") (pintype "bidirectional"))
      (node (ref "SBRIO_MEZZANINE") (pin "237") (pinfunction "GND_237") (pintype "power_in"))
      (node (ref "SHTDWN_CONN") (pin "10") (pinfunction "5_10") (pintype "bidirectional"))
      (node (ref "SHTDWN_CONN") (pin "9") (pinfunction "5_9") (pintype "bidirectional"))
      (node (ref "U1") (pin "P$2") (pinfunction "GND_P$2") (pintype "bidirectional"))
    )
    (net (code "74") (name "IMD_OK_IN") (class "Default")
      (node (ref "5225-3.3M5-TR(5)") (pin "P$1") (pinfunction "3~{16V_IN}_P$1") (pintype "bidirectional"))
      (node (ref "ACCUMULATOR_CONN") (pin "8") (pinfunction "8_8") (pintype "passive"))
      (node (ref "R2") (pin "1") (pinfunction "1_1") (pintype "passive"))
    )
    (net (code "75") (name "IMD_OUT") (class "Default")
      (node (ref "IC3") (pin "14") (pinfunction "OUT3_14") (pintype "output"))
      (node (ref "TUB_CONN") (pin "5") (pinfunction "KL_5") (pintype "passive"))
    )
    (net (code "76") (name "LAP_TIMER_IN") (class "Default")
      (node (ref "R36") (pin "2") (pinfunction "2_2") (pintype "passive"))
      (node (ref "TUB_CONN") (pin "2") (pinfunction "KL_2") (pintype "passive"))
      (node (ref "U1") (pin "P$8") (pinfunction "B1_P$8") (pintype "bidirectional"))
    )
    (net (code "77") (name "LATCH_OK") (class "Default")
      (node (ref "5525-3.3YM5-TR(2)") (pin "P$1") (pinfunction "3~{16V_IN}_P$1") (pintype "bidirectional"))
      (node (ref "AIO_PO_CONN") (pin "8") (pinfunction "KL_8") (pintype "passive"))
      (node (ref "R5") (pin "1") (pinfunction "1_1") (pintype "passive"))
    )
    (net (code "78") (name "Net-(4401-7-F(1)-B)") (class "Default")
      (node (ref "4401-7-F(1)") (pin "P$2") (pinfunction "B_P$2") (pintype "passive"))
      (node (ref "R15") (pin "2") (pinfunction "2_2") (pintype "passive"))
    )
    (net (code "79") (name "Net-(4401-7-F(1)-C)") (class "Default")
      (node (ref "4401-7-F(1)") (pin "P$1") (pinfunction "C_P$1") (pintype "passive"))
      (node (ref "R12") (pin "1") (pinfunction "1_1") (pintype "passive"))
    )
    (net (code "80") (name "Net-(4401-7-F(2)-B)") (class "Default")
      (node (ref "4401-7-F(2)") (pin "P$2") (pinfunction "B_P$2") (pintype "passive"))
      (node (ref "R16") (pin "2") (pinfunction "2_2") (pintype "passive"))
    )
    (net (code "81") (name "Net-(4401-7-F(2)-C)") (class "Default")
      (node (ref "4401-7-F(2)") (pin "P$1") (pinfunction "C_P$1") (pintype "passive"))
      (node (ref "R11") (pin "1") (pinfunction "1_1") (pintype "passive"))
    )
    (net (code "82") (name "Net-(4403-7-F(2)-B)") (class "Default")
      (node (ref "4403-7-F(2)") (pin "P$2") (pinfunction "B_P$2") (pintype "passive"))
      (node (ref "R12") (pin "2") (pinfunction "2_2") (pintype "passive"))
    )
    (net (code "83") (name "Net-(4403-7-F(2)-C)") (class "Default")
      (node (ref "4403-7-F(2)") (pin "P$1") (pinfunction "C_P$1") (pintype "passive"))
      (node (ref "F18") (pin "2") (pinfunction "2_2") (pintype "passive"))
    )
    (net (code "84") (name "Net-(4403-7-F-B)") (class "Default")
      (node (ref "4403-7-F") (pin "P$2") (pinfunction "B_P$2") (pintype "passive"))
      (node (ref "R11") (pin "2") (pinfunction "2_2") (pintype "passive"))
    )
    (net (code "85") (name "Net-(4403-7-F-C)") (class "Default")
      (node (ref "4403-7-F") (pin "P$1") (pinfunction "C_P$1") (pintype "passive"))
      (node (ref "F17") (pin "2") (pinfunction "2_2") (pintype "passive"))
    )
    (net (code "86") (name "Net-(5238B-7-F-A)") (class "Default")
      (node (ref "5238B-7-F") (pin "P$2") (pinfunction "A_P$2") (pintype "passive"))
      (node (ref "R13") (pin "2") (pinfunction "2_2") (pintype "passive"))
      (node (ref "SBRIO_ANALOG") (pin "P$2") (pinfunction "AI0_P$2") (pintype "input"))
    )
    (net (code "87") (name "Net-(AIO_PO_CONNB-KL)") (class "Default")
      (node (ref "AIO_PO_CONN") (pin "10") (pinfunction "KL_10") (pintype "passive"))
      (node (ref "F20") (pin "2") (pinfunction "2_2") (pintype "passive"))
    )
    (net (code "88") (name "Net-(AIO_PO_CONNC-KL)") (class "Default")
      (node (ref "AIO_PO_CONN") (pin "11") (pinfunction "KL_11") (pintype "passive"))
      (node (ref "F21") (pin "2") (pinfunction "2_2") (pintype "passive"))
    )
    (net (code "89") (name "Net-(AIO_PO_CONND-KL)") (class "Default")
      (node (ref "AIO_PO_CONN") (pin "12") (pinfunction "KL_12") (pintype "passive"))
      (node (ref "F22") (pin "2") (pinfunction "2_2") (pintype "passive"))
    )
    (net (code "90") (name "Net-(AIO_PO_CONNI-KL)") (class "Default")
      (node (ref "AIO_PO_CONN") (pin "2") (pinfunction "KL_2") (pintype "passive"))
      (node (ref "F16") (pin "2") (pinfunction "2_2") (pintype "passive"))
    )
    (net (code "91") (name "Net-(AIO_PO_CONNP-KL)") (class "Default")
      (node (ref "AIO_PO_CONN") (pin "9") (pinfunction "KL_9") (pintype "passive"))
      (node (ref "F15") (pin "2") (pinfunction "2_2") (pintype "passive"))
    )
    (net (code "92") (name "Net-(BSPD_CONN-5-Pad10)") (class "Default")
      (node (ref "BSPD_CONN") (pin "10") (pinfunction "5_10") (pintype "bidirectional"))
      (node (ref "BSPD_CONN") (pin "9") (pinfunction "5_9") (pintype "bidirectional"))
      (node (ref "F6") (pin "1") (pinfunction "1_1") (pintype "passive"))
    )
    (net (code "93") (name "Net-(C13-Pad1)") (class "Default")
      (node (ref "C13") (pin "1") (pinfunction "1_1") (pintype "passive"))
      (node (ref "R35") (pin "2") (pinfunction "2_2") (pintype "passive"))
    )
    (net (code "94") (name "Net-(F1-Pad2)") (class "Default")
      (node (ref "F1") (pin "2") (pinfunction "2_2") (pintype "passive"))
      (node (ref "SHTDWN_CONN") (pin "5") (pinfunction "3_5") (pintype "bidirectional"))
      (node (ref "SHTDWN_CONN") (pin "6") (pinfunction "3_6") (pintype "bidirectional"))
    )
    (net (code "95") (name "Net-(F2-Pad2)") (class "Default")
      (node (ref "F2") (pin "2") (pinfunction "2_2") (pintype "passive"))
      (node (ref "SHTDWN_CONN") (pin "3") (pinfunction "2_3") (pintype "bidirectional"))
      (node (ref "SHTDWN_CONN") (pin "4") (pinfunction "2_4") (pintype "bidirectional"))
    )
    (net (code "96") (name "Net-(F14-Pad2)") (class "Default")
      (node (ref "F14") (pin "2") (pinfunction "2_2") (pintype "passive"))
      (node (ref "SHTDWN_CONN") (pin "1") (pinfunction "1_1") (pintype "bidirectional"))
      (node (ref "SHTDWN_CONN") (pin "2") (pinfunction "1_2") (pintype "bidirectional"))
    )
    (net (code "97") (name "Net-(GYRO-PLL)") (class "Default")
      (node (ref "C13") (pin "2") (pinfunction "2_2") (pintype "passive"))
      (node (ref "C14") (pin "2") (pinfunction "2_2") (pintype "passive"))
      (node (ref "GYRO") (pin "14") (pinfunction "PLL_14") (pintype "bidirectional"))
    )
    (net (code "98") (name "PO2") (class "Default")
      (node (ref "AIO_PO_CONN") (pin "15") (pinfunction "KL_15") (pintype "passive"))
      (node (ref "IC1") (pin "17") (pinfunction "OUT2_17") (pintype "output"))
    )
    (net (code "99") (name "PO3") (class "Default")
      (node (ref "AIO_PO_CONN") (pin "14") (pinfunction "KL_14") (pintype "passive"))
      (node (ref "IC1") (pin "14") (pinfunction "OUT3_14") (pintype "output"))
    )
    (net (code "100") (name "PO4") (class "Default")
      (node (ref "AIO_PO_CONN") (pin "13") (pinfunction "KL_13") (pintype "passive"))
      (node (ref "IC1") (pin "13") (pinfunction "OUT4_13") (pintype "output"))
    )
    (net (code "101") (name "SHIELD") (class "Default")
      (node (ref "ACCUMULATOR_CONN") (pin "6") (pinfunction "6_6") (pintype "passive"))
      (node (ref "SBRIO_CAN") (pin "P$10") (pinfunction "SHIELD_P$10") (pintype "power_in"))
      (node (ref "SBRIO_CAN") (pin "P$5") (pinfunction "SHIELD_P$5") (pintype "power_in"))
    )
    (net (code "102") (name "SHUTDOWN_1") (class "Default")
      (node (ref "F14") (pin "1") (pinfunction "1_1") (pintype "passive"))
      (node (ref "IC2") (pin "17") (pinfunction "OUT2_17") (pintype "output"))
    )
    (net (code "103") (name "SHUTDOWN_2") (class "Default")
      (node (ref "F2") (pin "1") (pinfunction "1_1") (pintype "passive"))
      (node (ref "IC2") (pin "14") (pinfunction "OUT3_14") (pintype "output"))
    )
    (net (code "104") (name "SHUTDOWN_3") (class "Default")
      (node (ref "F1") (pin "1") (pinfunction "1_1") (pintype "passive"))
      (node (ref "IC2") (pin "13") (pinfunction "OUT4_13") (pintype "output"))
    )
    (net (code "105") (name "STEERING_POS") (class "Default")
      (node (ref "R17") (pin "2") (pinfunction "2_2") (pintype "passive"))
      (node (ref "SBRIO_ANALOG") (pin "P$21") (pinfunction "AI14_P$21") (pintype "input"))
      (node (ref "SBRIO_AUX") (pin "P$39") (pinfunction "AI14_P$39") (pintype "bidirectional"))
      (node (ref "TUB_CONN") (pin "16") (pinfunction "KL_16") (pintype "passive"))
    )
    (net (code "106") (name "THROTTLE_IN_1") (class "Default")
      (node (ref "R20") (pin "2") (pinfunction "2_2") (pintype "passive"))
      (node (ref "SBRIO_ANALOG") (pin "P$18") (pinfunction "AI5_P$18") (pintype "input"))
      (node (ref "TUB_CONN") (pin "13") (pinfunction "KL_13") (pintype "passive"))
    )
    (net (code "107") (name "THROTTLE_IN_2") (class "Default")
      (node (ref "R21") (pin "2") (pinfunction "2_2") (pintype "passive"))
      (node (ref "SBRIO_ANALOG") (pin "P$20") (pinfunction "AI6_P$20") (pintype "input"))
      (node (ref "TUB_CONN") (pin "14") (pinfunction "KL_14") (pintype "passive"))
    )
    (net (code "108") (name "THROTTLE_OK_OUT") (class "Default")
      (node (ref "F6") (pin "2") (pinfunction "2_2") (pintype "passive"))
      (node (ref "IC2") (pin "18") (pinfunction "OUT1_18") (pintype "output"))
    )
    (net (code "109") (name "WS1") (class "Default")
      (node (ref "LEVEL_SHIFTER") (pin "13") (pinfunction "B1_13") (pintype "bidirectional"))
      (node (ref "WHEEL") (pin "1") (pinfunction "1_1") (pintype "passive"))
    )
    (net (code "110") (name "WS2") (class "Default")
      (node (ref "LEVEL_SHIFTER") (pin "12") (pinfunction "B2_12") (pintype "bidirectional"))
      (node (ref "WHEEL") (pin "2") (pinfunction "1_2") (pintype "passive"))
    )
    (net (code "111") (name "WS3") (class "Default")
      (node (ref "LEVEL_SHIFTER") (pin "11") (pinfunction "B3_11") (pintype "bidirectional"))
      (node (ref "WHEEL") (pin "3") (pinfunction "1_3") (pintype "passive"))
    )
    (net (code "112") (name "WS4") (class "Default")
      (node (ref "LEVEL_SHIFTER") (pin "10") (pinfunction "B4_10") (pintype "bidirectional"))
      (node (ref "WHEEL") (pin "4") (pinfunction "1_4") (pintype "passive"))
    )
    (net (code "113") (name "unconnected-(3.3V_REG-Pad6)") (class "Default")
      (node (ref "3.3V_REG") (pin "6") (pinfunction "6_6") (pintype "bidirectional"))
    )
    (net (code "114") (name "unconnected-(ACCEL-NC-Pad3)") (class "Default")
      (node (ref "ACCEL") (pin "3") (pinfunction "NC_3") (pintype "bidirectional"))
    )
    (net (code "115") (name "unconnected-(ACCEL-NC-Pad10)") (class "Default")
      (node (ref "ACCEL") (pin "10") (pinfunction "NC_10") (pintype "bidirectional"))
    )
    (net (code "116") (name "unconnected-(ACCEL-NC-Pad11)") (class "Default")
      (node (ref "ACCEL") (pin "11") (pinfunction "NC_11") (pintype "bidirectional"))
    )
    (net (code "117") (name "unconnected-(AIO_PO_CONNA-KL-Pad1)") (class "Default")
      (node (ref "AIO_PO_CONN") (pin "1") (pinfunction "KL_1") (pintype "passive"))
    )
    (net (code "118") (name "unconnected-(AIO_PO_CONNJ-KL-Pad3)") (class "Default")
      (node (ref "AIO_PO_CONN") (pin "3") (pinfunction "KL_3") (pintype "passive"))
    )
    (net (code "119") (name "unconnected-(IC1A-ST1{slash}2-Pad4)") (class "Default")
      (node (ref "IC1") (pin "4") (pinfunction "ST1/2_4") (pintype "input"))
    )
    (net (code "120") (name "unconnected-(IC1A-ST3{slash}4-Pad8)") (class "Default")
      (node (ref "IC1") (pin "8") (pinfunction "ST3/4_8") (pintype "input"))
    )
    (net (code "121") (name "unconnected-(IC2A-ST1{slash}2-Pad4)") (class "Default")
      (node (ref "IC2") (pin "4") (pinfunction "ST1/2_4") (pintype "input"))
    )
    (net (code "122") (name "unconnected-(IC2A-ST3{slash}4-Pad8)") (class "Default")
      (node (ref "IC2") (pin "8") (pinfunction "ST3/4_8") (pintype "input"))
    )
    (net (code "123") (name "unconnected-(IC3A-ST1{slash}2-Pad4)") (class "Default")
      (node (ref "IC3") (pin "4") (pinfunction "ST1/2_4") (pintype "input"))
    )
    (net (code "124") (name "unconnected-(IC3A-ST3{slash}4-Pad8)") (class "Default")
      (node (ref "IC3") (pin "8") (pinfunction "ST3/4_8") (pintype "input"))
    )
    (net (code "125") (name "unconnected-(SBRIO_ANALOG-DIO_0-PadP$44)") (class "Default")
      (node (ref "SBRIO_ANALOG") (pin "P$44") (pinfunction "DIO_0_P$44") (pintype "bidirectional"))
    )
    (net (code "126") (name "unconnected-(SBRIO_ANALOG-DIO_1-PadP$46)") (class "Default")
      (node (ref "SBRIO_ANALOG") (pin "P$46") (pinfunction "DIO_1_P$46") (pintype "bidirectional"))
    )
    (net (code "127") (name "unconnected-(SBRIO_ANALOG-DIO_2-PadP$48)") (class "Default")
      (node (ref "SBRIO_ANALOG") (pin "P$48") (pinfunction "DIO_2_P$48") (pintype "bidirectional"))
    )
    (net (code "128") (name "unconnected-(SBRIO_ANALOG-DIO_3-PadP$50)") (class "Default")
      (node (ref "SBRIO_ANALOG") (pin "P$50") (pinfunction "DIO_3_P$50") (pintype "bidirectional"))
    )
    (net (code "129") (name "unconnected-(SBRIO_AUX-DIO16-PadP$16)") (class "Default")
      (node (ref "SBRIO_AUX") (pin "P$16") (pinfunction "DIO16_P$16") (pintype "bidirectional"))
    )
    (net (code "130") (name "unconnected-(SBRIO_AUX-DIO17-PadP$14)") (class "Default")
      (node (ref "SBRIO_AUX") (pin "P$14") (pinfunction "DIO17_P$14") (pintype "bidirectional"))
    )
    (net (code "131") (name "unconnected-(SBRIO_AUX-DIO39-PadP$6)") (class "Default")
      (node (ref "SBRIO_AUX") (pin "P$6") (pinfunction "DIO39_P$6") (pintype "bidirectional"))
    )
    (net (code "132") (name "unconnected-(SBRIO_AUX-E-STOP-PadP$4)") (class "Default")
      (node (ref "SBRIO_AUX") (pin "P$4") (pinfunction "E-STOP_P$4") (pintype "bidirectional"))
    )
    (net (code "133") (name "unconnected-(SBRIO_AUX-LATCH-PadP$2)") (class "Default")
      (node (ref "SBRIO_AUX") (pin "P$2") (pinfunction "LATCH_P$2") (pintype "bidirectional"))
    )
    (net (code "134") (name "unconnected-(SBRIO_AUX-POS_AIR-PadP$1)") (class "Default")
      (node (ref "SBRIO_AUX") (pin "P$1") (pinfunction "POS_AIR_P$1") (pintype "bidirectional"))
    )
    (net (code "135") (name "unconnected-(SBRIO_MEZZANINE-DIO2-Pad210)") (class "Default")
      (node (ref "SBRIO_MEZZANINE") (pin "210") (pinfunction "DIO2_210") (pintype "bidirectional"))
    )
    (net (code "136") (name "unconnected-(SBRIO_MEZZANINE-DIO3-Pad198)") (class "Default")
      (node (ref "SBRIO_MEZZANINE") (pin "198") (pinfunction "DIO3_198") (pintype "bidirectional"))
    )
    (net (code "137") (name "unconnected-(SBRIO_MEZZANINE-DIO13-Pad108)") (class "Default")
      (node (ref "SBRIO_MEZZANINE") (pin "108") (pinfunction "DIO13_108") (pintype "bidirectional"))
    )
    (net (code "138") (name "unconnected-(SBRIO_MEZZANINE-DIO14-Pad102)") (class "Default")
      (node (ref "SBRIO_MEZZANINE") (pin "102") (pinfunction "DIO14_102") (pintype "bidirectional"))
    )
    (net (code "139") (name "unconnected-(SBRIO_MEZZANINE-DIO15-Pad90)") (class "Default")
      (node (ref "SBRIO_MEZZANINE") (pin "90") (pinfunction "DIO15_90") (pintype "bidirectional"))
    )
    (net (code "140") (name "unconnected-(SBRIO_MEZZANINE-DIO19-Pad207)") (class "Default")
      (node (ref "SBRIO_MEZZANINE") (pin "207") (pinfunction "DIO19_207") (pintype "bidirectional"))
    )
    (net (code "141") (name "unconnected-(SBRIO_MEZZANINE-DIO20-Pad195)") (class "Default")
      (node (ref "SBRIO_MEZZANINE") (pin "195") (pinfunction "DIO20_195") (pintype "bidirectional"))
    )
    (net (code "142") (name "unconnected-(SBRIO_MEZZANINE-DIO21-Pad189)") (class "Default")
      (node (ref "SBRIO_MEZZANINE") (pin "189") (pinfunction "DIO21_189") (pintype "bidirectional"))
    )
    (net (code "143") (name "unconnected-(SBRIO_MEZZANINE-DIO22-Pad177)") (class "Default")
      (node (ref "SBRIO_MEZZANINE") (pin "177") (pinfunction "DIO22_177") (pintype "bidirectional"))
    )
    (net (code "144") (name "unconnected-(SBRIO_MEZZANINE-DIO23-Pad171)") (class "Default")
      (node (ref "SBRIO_MEZZANINE") (pin "171") (pinfunction "DIO23_171") (pintype "bidirectional"))
    )
    (net (code "145") (name "unconnected-(SBRIO_MEZZANINE-DIO24-Pad159)") (class "Default")
      (node (ref "SBRIO_MEZZANINE") (pin "159") (pinfunction "DIO24_159") (pintype "bidirectional"))
    )
    (net (code "146") (name "unconnected-(SBRIO_MEZZANINE-DIO25-Pad153)") (class "Default")
      (node (ref "SBRIO_MEZZANINE") (pin "153") (pinfunction "DIO25_153") (pintype "bidirectional"))
    )
    (net (code "147") (name "unconnected-(SBRIO_MEZZANINE-DIO26-Pad141)") (class "Default")
      (node (ref "SBRIO_MEZZANINE") (pin "141") (pinfunction "DIO26_141") (pintype "bidirectional"))
    )
    (net (code "148") (name "unconnected-(SBRIO_MEZZANINE-DIO27-Pad135)") (class "Default")
      (node (ref "SBRIO_MEZZANINE") (pin "135") (pinfunction "DIO27_135") (pintype "bidirectional"))
    )
    (net (code "149") (name "unconnected-(SBRIO_MEZZANINE-DIO28-Pad123)") (class "Default")
      (node (ref "SBRIO_MEZZANINE") (pin "123") (pinfunction "DIO28_123") (pintype "bidirectional"))
    )
    (net (code "150") (name "unconnected-(SBRIO_MEZZANINE-DIO29-Pad117)") (class "Default")
      (node (ref "SBRIO_MEZZANINE") (pin "117") (pinfunction "DIO29_117") (pintype "bidirectional"))
    )
    (net (code "151") (name "unconnected-(SBRIO_MEZZANINE-DIO30-Pad105)") (class "Default")
      (node (ref "SBRIO_MEZZANINE") (pin "105") (pinfunction "DIO30_105") (pintype "bidirectional"))
    )
    (net (code "152") (name "unconnected-(SBRIO_MEZZANINE-DIO31-Pad99)") (class "Default")
      (node (ref "SBRIO_MEZZANINE") (pin "99") (pinfunction "DIO31_99") (pintype "bidirectional"))
    )
    (net (code "153") (name "unconnected-(SBRIO_MEZZANINE-DIO33-Pad215)") (class "Default")
      (node (ref "SBRIO_MEZZANINE") (pin "215") (pinfunction "DIO33_215") (pintype "bidirectional"))
    )
    (net (code "154") (name "unconnected-(SBRIO_MEZZANINE-DIO34-Pad203)") (class "Default")
      (node (ref "SBRIO_MEZZANINE") (pin "203") (pinfunction "DIO34_203") (pintype "bidirectional"))
    )
    (net (code "155") (name "unconnected-(SBRIO_MEZZANINE-DIO35-Pad197)") (class "Default")
      (node (ref "SBRIO_MEZZANINE") (pin "197") (pinfunction "DIO35_197") (pintype "bidirectional"))
    )
    (net (code "156") (name "unconnected-(SBRIO_MEZZANINE-DIO36-Pad185)") (class "Default")
      (node (ref "SBRIO_MEZZANINE") (pin "185") (pinfunction "DIO36_185") (pintype "bidirectional"))
    )
    (net (code "157") (name "unconnected-(SBRIO_MEZZANINE-DIO46-Pad95)") (class "Default")
      (node (ref "SBRIO_MEZZANINE") (pin "95") (pinfunction "DIO46_95") (pintype "bidirectional"))
    )
    (net (code "158") (name "unconnected-(SBRIO_MEZZANINE-DIO47-Pad89)") (class "Default")
      (node (ref "SBRIO_MEZZANINE") (pin "89") (pinfunction "DIO47_89") (pintype "bidirectional"))
    )
    (net (code "159") (name "unconnected-(SBRIO_MEZZANINE-DIO49-Pad218)") (class "Default")
      (node (ref "SBRIO_MEZZANINE") (pin "218") (pinfunction "DIO49_218") (pintype "bidirectional"))
    )
    (net (code "160") (name "unconnected-(SBRIO_MEZZANINE-DIO50-Pad212)") (class "Default")
      (node (ref "SBRIO_MEZZANINE") (pin "212") (pinfunction "DIO50_212") (pintype "bidirectional"))
    )
    (net (code "161") (name "unconnected-(SBRIO_MEZZANINE-DIO51-Pad200)") (class "Default")
      (node (ref "SBRIO_MEZZANINE") (pin "200") (pinfunction "DIO51_200") (pintype "bidirectional"))
    )
    (net (code "162") (name "unconnected-(SBRIO_MEZZANINE-DIO52-Pad194)") (class "Default")
      (node (ref "SBRIO_MEZZANINE") (pin "194") (pinfunction "DIO52_194") (pintype "bidirectional"))
    )
    (net (code "163") (name "unconnected-(SBRIO_MEZZANINE-DIO53-Pad182)") (class "Default")
      (node (ref "SBRIO_MEZZANINE") (pin "182") (pinfunction "DIO53_182") (pintype "bidirectional"))
    )
    (net (code "164") (name "unconnected-(SBRIO_MEZZANINE-DIO54-Pad176)") (class "Default")
      (node (ref "SBRIO_MEZZANINE") (pin "176") (pinfunction "DIO54_176") (pintype "bidirectional"))
    )
    (net (code "165") (name "unconnected-(SBRIO_MEZZANINE-DIO55-Pad164)") (class "Default")
      (node (ref "SBRIO_MEZZANINE") (pin "164") (pinfunction "DIO55_164") (pintype "bidirectional"))
    )
    (net (code "166") (name "unconnected-(SBRIO_MEZZANINE-DIO56-Pad158)") (class "Default")
      (node (ref "SBRIO_MEZZANINE") (pin "158") (pinfunction "DIO56_158") (pintype "bidirectional"))
    )
    (net (code "167") (name "unconnected-(SBRIO_MEZZANINE-DIO57-Pad146)") (class "Default")
      (node (ref "SBRIO_MEZZANINE") (pin "146") (pinfunction "DIO57_146") (pintype "bidirectional"))
    )
    (net (code "168") (name "unconnected-(SBRIO_MEZZANINE-DIO58-Pad140)") (class "Default")
      (node (ref "SBRIO_MEZZANINE") (pin "140") (pinfunction "DIO58_140") (pintype "bidirectional"))
    )
    (net (code "169") (name "unconnected-(SBRIO_MEZZANINE-DIO59-Pad128)") (class "Default")
      (node (ref "SBRIO_MEZZANINE") (pin "128") (pinfunction "DIO59_128") (pintype "bidirectional"))
    )
    (net (code "170") (name "unconnected-(SBRIO_MEZZANINE-DIO60-Pad122)") (class "Default")
      (node (ref "SBRIO_MEZZANINE") (pin "122") (pinfunction "DIO60_122") (pintype "bidirectional"))
    )
    (net (code "171") (name "unconnected-(SBRIO_MEZZANINE-DIO61-Pad110)") (class "Default")
      (node (ref "SBRIO_MEZZANINE") (pin "110") (pinfunction "DIO61_110") (pintype "bidirectional"))
    )
    (net (code "172") (name "unconnected-(SBRIO_MEZZANINE-DIO62-Pad104)") (class "Default")
      (node (ref "SBRIO_MEZZANINE") (pin "104") (pinfunction "DIO62_104") (pintype "bidirectional"))
    )
    (net (code "173") (name "unconnected-(SBRIO_MEZZANINE-DIO63-Pad92)") (class "Default")
      (node (ref "SBRIO_MEZZANINE") (pin "92") (pinfunction "DIO63_92") (pintype "bidirectional"))
    )
    (net (code "174") (name "unconnected-(SBRIO_MEZZANINE-DIO66-Pad208)") (class "Default")
      (node (ref "SBRIO_MEZZANINE") (pin "208") (pinfunction "DIO66_208") (pintype "bidirectional"))
    )
    (net (code "175") (name "unconnected-(SBRIO_MEZZANINE-DIO67-Pad202)") (class "Default")
      (node (ref "SBRIO_MEZZANINE") (pin "202") (pinfunction "DIO67_202") (pintype "bidirectional"))
    )
    (net (code "176") (name "unconnected-(SBRIO_MEZZANINE-DIO68-Pad190)") (class "Default")
      (node (ref "SBRIO_MEZZANINE") (pin "190") (pinfunction "DIO68_190") (pintype "bidirectional"))
    )
    (net (code "177") (name "unconnected-(SBRIO_MEZZANINE-DIO69-Pad184)") (class "Default")
      (node (ref "SBRIO_MEZZANINE") (pin "184") (pinfunction "DIO69_184") (pintype "bidirectional"))
    )
    (net (code "178") (name "unconnected-(SBRIO_MEZZANINE-DIO70-Pad172)") (class "Default")
      (node (ref "SBRIO_MEZZANINE") (pin "172") (pinfunction "DIO70_172") (pintype "bidirectional"))
    )
    (net (code "179") (name "unconnected-(SBRIO_MEZZANINE-DIO71-Pad166)") (class "Default")
      (node (ref "SBRIO_MEZZANINE") (pin "166") (pinfunction "DIO71_166") (pintype "bidirectional"))
    )
    (net (code "180") (name "unconnected-(SBRIO_MEZZANINE-DIO72-Pad154)") (class "Default")
      (node (ref "SBRIO_MEZZANINE") (pin "154") (pinfunction "DIO72_154") (pintype "bidirectional"))
    )
    (net (code "181") (name "unconnected-(SBRIO_MEZZANINE-DIO73-Pad148)") (class "Default")
      (node (ref "SBRIO_MEZZANINE") (pin "148") (pinfunction "DIO73_148") (pintype "bidirectional"))
    )
    (net (code "182") (name "unconnected-(SBRIO_MEZZANINE-DIO74-Pad136)") (class "Default")
      (node (ref "SBRIO_MEZZANINE") (pin "136") (pinfunction "DIO74_136") (pintype "bidirectional"))
    )
    (net (code "183") (name "unconnected-(SBRIO_MEZZANINE-DIO75-Pad130)") (class "Default")
      (node (ref "SBRIO_MEZZANINE") (pin "130") (pinfunction "DIO75_130") (pintype "bidirectional"))
    )
    (net (code "184") (name "unconnected-(SBRIO_MEZZANINE-DIO76-Pad118)") (class "Default")
      (node (ref "SBRIO_MEZZANINE") (pin "118") (pinfunction "DIO76_118") (pintype "bidirectional"))
    )
    (net (code "185") (name "unconnected-(SBRIO_MEZZANINE-DIO77-Pad112)") (class "Default")
      (node (ref "SBRIO_MEZZANINE") (pin "112") (pinfunction "DIO77_112") (pintype "bidirectional"))
    )
    (net (code "186") (name "unconnected-(SBRIO_MEZZANINE-DIO78-Pad100)") (class "Default")
      (node (ref "SBRIO_MEZZANINE") (pin "100") (pinfunction "DIO78_100") (pintype "bidirectional"))
    )
    (net (code "187") (name "unconnected-(SBRIO_MEZZANINE-DIO79-Pad94)") (class "Default")
      (node (ref "SBRIO_MEZZANINE") (pin "94") (pinfunction "DIO79_94") (pintype "bidirectional"))
    )
    (net (code "188") (name "unconnected-(SBRIO_MEZZANINE-DIO80-Pad235)") (class "Default")
      (node (ref "SBRIO_MEZZANINE") (pin "235") (pinfunction "DIO80_235") (pintype "bidirectional"))
    )
    (net (code "189") (name "unconnected-(SBRIO_MEZZANINE-DIO82-Pad217)") (class "Default")
      (node (ref "SBRIO_MEZZANINE") (pin "217") (pinfunction "DIO82_217") (pintype "bidirectional"))
    )
    (net (code "190") (name "unconnected-(SBRIO_MEZZANINE-DIO84-Pad199)") (class "Default")
      (node (ref "SBRIO_MEZZANINE") (pin "199") (pinfunction "DIO84_199") (pintype "bidirectional"))
    )
    (net (code "191") (name "unconnected-(SBRIO_MEZZANINE-DIO89-Pad151)") (class "Default")
      (node (ref "SBRIO_MEZZANINE") (pin "151") (pinfunction "DIO89_151") (pintype "bidirectional"))
    )
    (net (code "192") (name "unconnected-(U1-A2-PadP$4)") (class "Default")
      (node (ref "U1") (pin "P$4") (pinfunction "A2_P$4") (pintype "bidirectional"))
    )
    (net (code "193") (name "unconnected-(U1-B2-PadP$1)") (class "Default")
      (node (ref "U1") (pin "P$1") (pinfunction "B2_P$1") (pintype "bidirectional"))
    )
  )
)
